# C1316G.net
KiCad netlist of a schematic drawn in EAGLE
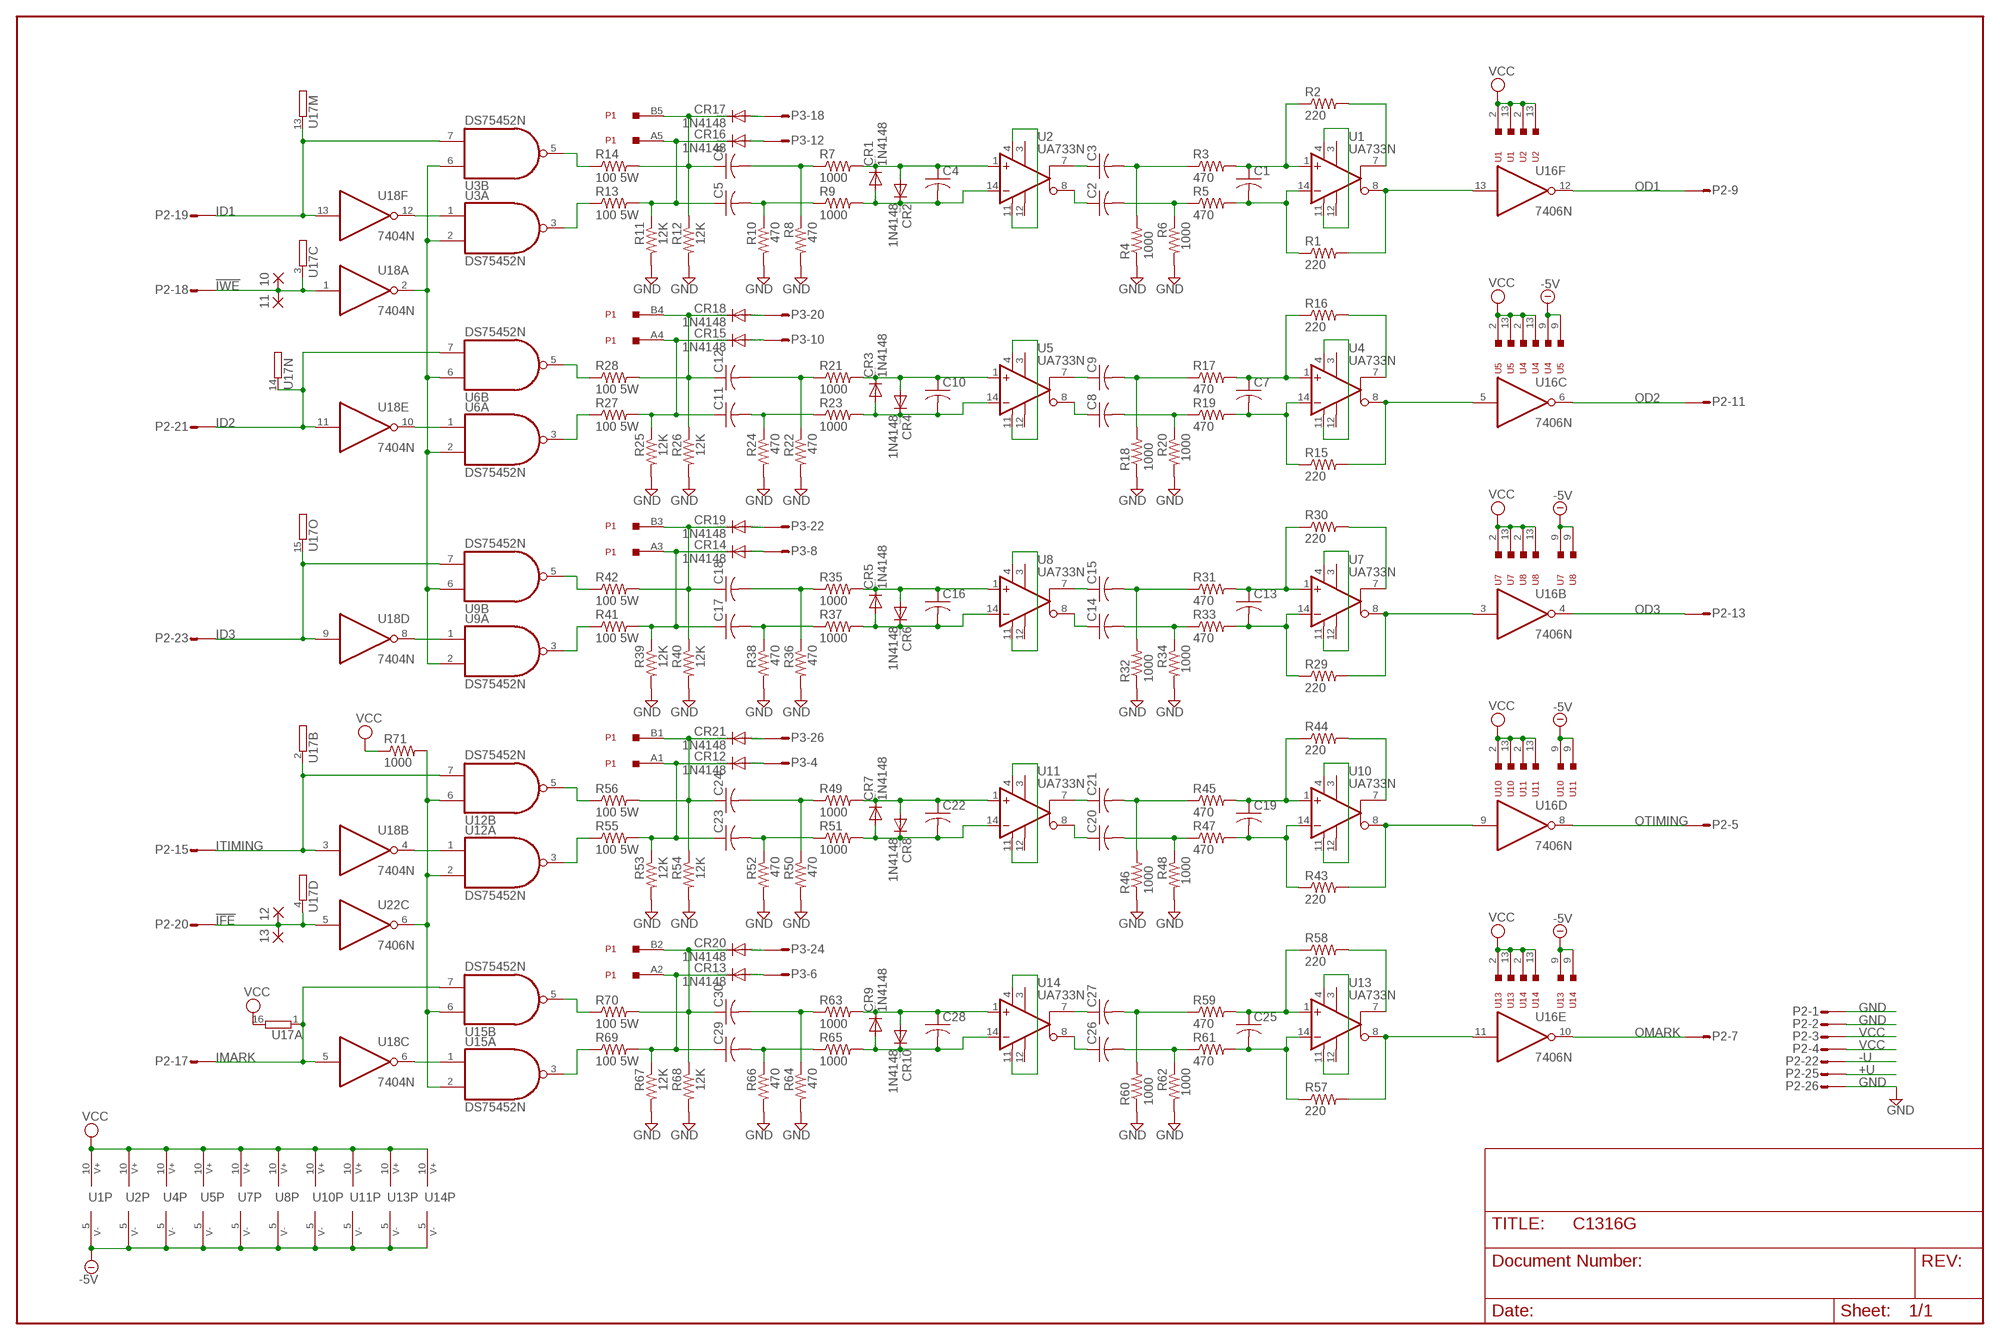
[diagram p0: schematic, sheet 1, part 1 of 2]
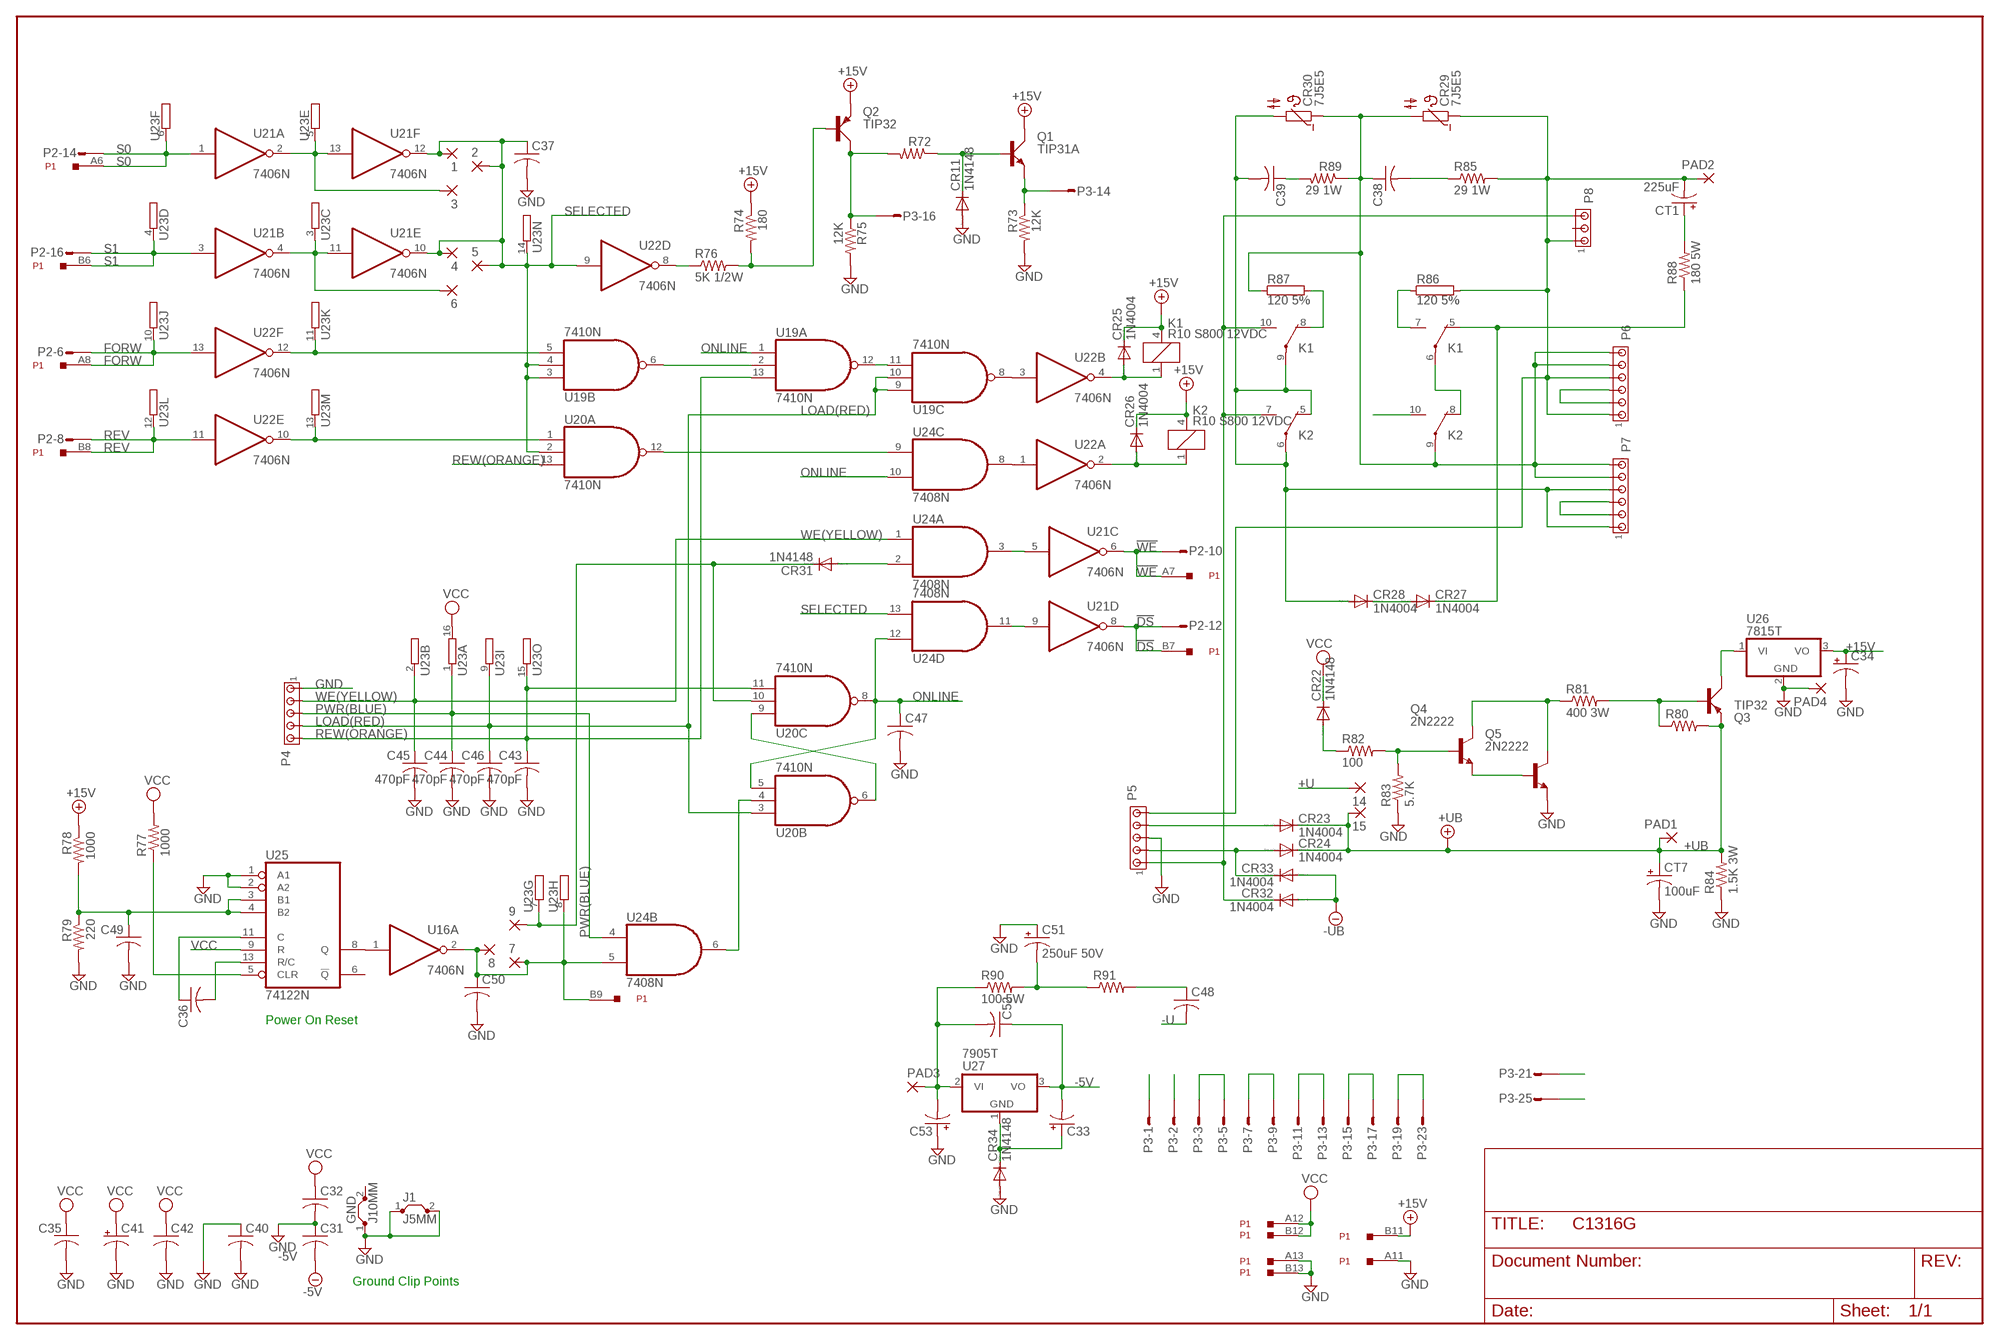
[diagram p1: schematic, sheet 1, part 2 of 2]

(export (version "E")
  (design (tool "Eeschema 10.0.6"))
  (components
    (comp (ref "1")
      (value "1,6/0,8")
      (footprint "eagle-import:1,6_0,8")
      (libsource (lib "eagle-import") (part "1,6/0,8"))
    )
    (comp (ref "2")
      (value "1,6/0,8")
      (footprint "eagle-import:1,6_0,8")
      (libsource (lib "eagle-import") (part "1,6/0,8"))
    )
    (comp (ref "3")
      (value "1,6/0,8")
      (footprint "eagle-import:1,6_0,8")
      (libsource (lib "eagle-import") (part "1,6/0,8"))
    )
    (comp (ref "4")
      (value "1,6/0,8")
      (footprint "eagle-import:1,6_0,8")
      (libsource (lib "eagle-import") (part "1,6/0,8"))
    )
    (comp (ref "5")
      (value "1,6/0,8")
      (footprint "eagle-import:1,6_0,8")
      (libsource (lib "eagle-import") (part "1,6/0,8"))
    )
    (comp (ref "6")
      (value "1,6/0,8")
      (footprint "eagle-import:1,6_0,8")
      (libsource (lib "eagle-import") (part "1,6/0,8"))
    )
    (comp (ref "7")
      (value "1,6/0,8")
      (footprint "eagle-import:1,6_0,8")
      (libsource (lib "eagle-import") (part "1,6/0,8"))
    )
    (comp (ref "8")
      (value "1,6/0,8")
      (footprint "eagle-import:1,6_0,8")
      (libsource (lib "eagle-import") (part "1,6/0,8"))
    )
    (comp (ref "9")
      (value "1,6/0,8")
      (footprint "eagle-import:1,6_0,8")
      (libsource (lib "eagle-import") (part "1,6/0,8"))
    )
    (comp (ref "10")
      (value "1,6/0,8")
      (footprint "eagle-import:1,6_0,8")
      (libsource (lib "eagle-import") (part "1,6/0,8"))
    )
    (comp (ref "11")
      (value "1,6/0,8")
      (footprint "eagle-import:1,6_0,8")
      (libsource (lib "eagle-import") (part "1,6/0,8"))
    )
    (comp (ref "12")
      (value "1,6/0,8")
      (footprint "eagle-import:1,6_0,8")
      (libsource (lib "eagle-import") (part "1,6/0,8"))
    )
    (comp (ref "13")
      (value "1,6/0,8")
      (footprint "eagle-import:1,6_0,8")
      (libsource (lib "eagle-import") (part "1,6/0,8"))
    )
    (comp (ref "14")
      (value "1,6/0,8")
      (footprint "eagle-import:1,6_0,8")
      (libsource (lib "eagle-import") (part "1,6/0,8"))
    )
    (comp (ref "15")
      (value "1,6/0,8")
      (footprint "eagle-import:1,6_0,8")
      (libsource (lib "eagle-import") (part "1,6/0,8"))
    )
    (comp (ref "C1")
      (value "C-US102-043X133")
      (footprint "eagle-import:C102-043X133")
      (libsource (lib "eagle-import") (part "C-US102-043X133"))
    )
    (comp (ref "C2")
      (value "C-US050-025X075")
      (footprint "eagle-import:C050-025X075")
      (libsource (lib "eagle-import") (part "C-US050-025X075"))
    )
    (comp (ref "C3")
      (value "C-US050-025X075")
      (footprint "eagle-import:C050-025X075")
      (libsource (lib "eagle-import") (part "C-US050-025X075"))
    )
    (comp (ref "C4")
      (value "C-US102-043X133")
      (footprint "eagle-import:C102-043X133")
      (libsource (lib "eagle-import") (part "C-US102-043X133"))
    )
    (comp (ref "C5")
      (value "C-US050-025X075")
      (footprint "eagle-import:C050-025X075")
      (libsource (lib "eagle-import") (part "C-US050-025X075"))
    )
    (comp (ref "C6")
      (value "C-US050-025X075")
      (footprint "eagle-import:C050-025X075")
      (libsource (lib "eagle-import") (part "C-US050-025X075"))
    )
    (comp (ref "C7")
      (value "C-US102-043X133")
      (footprint "eagle-import:C102-043X133")
      (libsource (lib "eagle-import") (part "C-US102-043X133"))
    )
    (comp (ref "C8")
      (value "C-US050-025X075")
      (footprint "eagle-import:C050-025X075")
      (libsource (lib "eagle-import") (part "C-US050-025X075"))
    )
    (comp (ref "C9")
      (value "C-US050-025X075")
      (footprint "eagle-import:C050-025X075")
      (libsource (lib "eagle-import") (part "C-US050-025X075"))
    )
    (comp (ref "C10")
      (value "C-US102-043X133")
      (footprint "eagle-import:C102-043X133")
      (libsource (lib "eagle-import") (part "C-US102-043X133"))
    )
    (comp (ref "C11")
      (value "C-US050-025X075")
      (footprint "eagle-import:C050-025X075")
      (libsource (lib "eagle-import") (part "C-US050-025X075"))
    )
    (comp (ref "C12")
      (value "C-US050-025X075")
      (footprint "eagle-import:C050-025X075")
      (libsource (lib "eagle-import") (part "C-US050-025X075"))
    )
    (comp (ref "C13")
      (value "C-US102-043X133")
      (footprint "eagle-import:C102-043X133")
      (libsource (lib "eagle-import") (part "C-US102-043X133"))
    )
    (comp (ref "C14")
      (value "C-US050-025X075")
      (footprint "eagle-import:C050-025X075")
      (libsource (lib "eagle-import") (part "C-US050-025X075"))
    )
    (comp (ref "C15")
      (value "C-US050-025X075")
      (footprint "eagle-import:C050-025X075")
      (libsource (lib "eagle-import") (part "C-US050-025X075"))
    )
    (comp (ref "C16")
      (value "C-US102-043X133")
      (footprint "eagle-import:C102-043X133")
      (libsource (lib "eagle-import") (part "C-US102-043X133"))
    )
    (comp (ref "C17")
      (value "C-US050-025X075")
      (footprint "eagle-import:C050-025X075")
      (libsource (lib "eagle-import") (part "C-US050-025X075"))
    )
    (comp (ref "C18")
      (value "C-US050-025X075")
      (footprint "eagle-import:C050-025X075")
      (libsource (lib "eagle-import") (part "C-US050-025X075"))
    )
    (comp (ref "C19")
      (value "C-US102-043X133")
      (footprint "eagle-import:C102-043X133")
      (libsource (lib "eagle-import") (part "C-US102-043X133"))
    )
    (comp (ref "C20")
      (value "C-US050-025X075")
      (footprint "eagle-import:C050-025X075")
      (libsource (lib "eagle-import") (part "C-US050-025X075"))
    )
    (comp (ref "C21")
      (value "C-US050-025X075")
      (footprint "eagle-import:C050-025X075")
      (libsource (lib "eagle-import") (part "C-US050-025X075"))
    )
    (comp (ref "C22")
      (value "C-US102-043X133")
      (footprint "eagle-import:C102-043X133")
      (libsource (lib "eagle-import") (part "C-US102-043X133"))
    )
    (comp (ref "C23")
      (value "C-US050-025X075")
      (footprint "eagle-import:C050-025X075")
      (libsource (lib "eagle-import") (part "C-US050-025X075"))
    )
    (comp (ref "C24")
      (value "C-US050-025X075")
      (footprint "eagle-import:C050-025X075")
      (libsource (lib "eagle-import") (part "C-US050-025X075"))
    )
    (comp (ref "C25")
      (value "C-US102-043X133")
      (footprint "eagle-import:C102-043X133")
      (libsource (lib "eagle-import") (part "C-US102-043X133"))
    )
    (comp (ref "C26")
      (value "C-US050-025X075")
      (footprint "eagle-import:C050-025X075")
      (libsource (lib "eagle-import") (part "C-US050-025X075"))
    )
    (comp (ref "C27")
      (value "C-US050-025X075")
      (footprint "eagle-import:C050-025X075")
      (libsource (lib "eagle-import") (part "C-US050-025X075"))
    )
    (comp (ref "C28")
      (value "C-US102-043X133")
      (footprint "eagle-import:C102-043X133")
      (libsource (lib "eagle-import") (part "C-US102-043X133"))
    )
    (comp (ref "C29")
      (value "C-US050-025X075")
      (footprint "eagle-import:C050-025X075")
      (libsource (lib "eagle-import") (part "C-US050-025X075"))
    )
    (comp (ref "C30")
      (value "C-US050-025X075")
      (footprint "eagle-import:C050-025X075")
      (libsource (lib "eagle-import") (part "C-US050-025X075"))
    )
    (comp (ref "C31")
      (value "C-US050-025X075")
      (footprint "eagle-import:C050-025X075")
      (libsource (lib "eagle-import") (part "C-US050-025X075"))
    )
    (comp (ref "C32")
      (value "C-US050-025X075")
      (footprint "eagle-import:C050-025X075")
      (libsource (lib "eagle-import") (part "C-US050-025X075"))
    )
    (comp (ref "C33")
      (value "CPOL-USB45181B")
      (footprint "eagle-import:B45181B")
      (libsource (lib "eagle-import") (part "CPOL-USB45181B"))
    )
    (comp (ref "C34")
      (value "CPOL-USB45181B")
      (footprint "eagle-import:B45181B")
      (libsource (lib "eagle-import") (part "CPOL-USB45181B"))
    )
    (comp (ref "C35")
      (value "C-US050-025X075")
      (footprint "eagle-import:C050-025X075")
      (libsource (lib "eagle-import") (part "C-US050-025X075"))
    )
    (comp (ref "C36")
      (value "C-US050-025X075")
      (footprint "eagle-import:C050-025X075")
      (libsource (lib "eagle-import") (part "C-US050-025X075"))
    )
    (comp (ref "C37")
      (value "C-US050-025X075")
      (footprint "eagle-import:C050-025X075")
      (libsource (lib "eagle-import") (part "C-US050-025X075"))
    )
    (comp (ref "C38")
      (value "C-US150-054X183")
      (footprint "eagle-import:C150-054X183")
      (libsource (lib "eagle-import") (part "C-US150-054X183"))
    )
    (comp (ref "C39")
      (value "C-US150-054X183")
      (footprint "eagle-import:C150-054X183")
      (libsource (lib "eagle-import") (part "C-US150-054X183"))
    )
    (comp (ref "C40")
      (value "C-US050-025X075")
      (footprint "eagle-import:C050-025X075")
      (libsource (lib "eagle-import") (part "C-US050-025X075"))
    )
    (comp (ref "C41")
      (value "CPOL-USE22-6AXIAL")
      (footprint "eagle-import:E22-6")
      (libsource (lib "eagle-import") (part "CPOL-USE22-6AXIAL"))
    )
    (comp (ref "C42")
      (value "C-US050-025X075")
      (footprint "eagle-import:C050-025X075")
      (libsource (lib "eagle-import") (part "C-US050-025X075"))
    )
    (comp (ref "C43")
      (value "470pF")
      (footprint "eagle-import:C050-025X075")
      (libsource (lib "eagle-import") (part "C-US050-025X075"))
    )
    (comp (ref "C44")
      (value "470pF")
      (footprint "eagle-import:C050-025X075")
      (libsource (lib "eagle-import") (part "C-US050-025X075"))
    )
    (comp (ref "C45")
      (value "470pF")
      (footprint "eagle-import:C050-025X075")
      (libsource (lib "eagle-import") (part "C-US050-025X075"))
    )
    (comp (ref "C46")
      (value "470pF")
      (footprint "eagle-import:C050-025X075")
      (libsource (lib "eagle-import") (part "C-US050-025X075"))
    )
    (comp (ref "C47")
      (value "C-US050-025X075")
      (footprint "eagle-import:C050-025X075")
      (libsource (lib "eagle-import") (part "C-US050-025X075"))
    )
    (comp (ref "C48")
      (value "C-US050-025X075")
      (footprint "eagle-import:C050-025X075")
      (libsource (lib "eagle-import") (part "C-US050-025X075"))
    )
    (comp (ref "C49")
      (value "C-US050-025X075")
      (footprint "eagle-import:C050-025X075")
      (libsource (lib "eagle-import") (part "C-US050-025X075"))
    )
    (comp (ref "C50")
      (value "C-US102-043X133")
      (footprint "eagle-import:C102-043X133")
      (libsource (lib "eagle-import") (part "C-US102-043X133"))
    )
    (comp (ref "C51")
      (value "250uF 50V")
      (footprint "eagle-import:E35-12")
      (libsource (lib "eagle-import") (part "CPOL-USE35-12AXIAL"))
    )
    (comp (ref "C52")
      (value "C-US050-025X075")
      (footprint "eagle-import:C050-025X075")
      (libsource (lib "eagle-import") (part "C-US050-025X075"))
    )
    (comp (ref "C53")
      (value "CPOL-USE22-6AXIAL")
      (footprint "eagle-import:E22-6")
      (libsource (lib "eagle-import") (part "CPOL-USE22-6AXIAL"))
    )
    (comp (ref "CR1")
      (value "1N4148")
      (footprint "eagle-import:DO35-10")
      (libsource (lib "eagle-import") (part "1N4148DO35-10"))
    )
    (comp (ref "CR2")
      (value "1N4148")
      (footprint "eagle-import:DO35-10")
      (libsource (lib "eagle-import") (part "1N4148DO35-10"))
    )
    (comp (ref "CR3")
      (value "1N4148")
      (footprint "eagle-import:DO35-10")
      (libsource (lib "eagle-import") (part "1N4148DO35-10"))
    )
    (comp (ref "CR4")
      (value "1N4148")
      (footprint "eagle-import:DO35-10")
      (libsource (lib "eagle-import") (part "1N4148DO35-10"))
    )
    (comp (ref "CR5")
      (value "1N4148")
      (footprint "eagle-import:DO35-10")
      (libsource (lib "eagle-import") (part "1N4148DO35-10"))
    )
    (comp (ref "CR6")
      (value "1N4148")
      (footprint "eagle-import:DO35-10")
      (libsource (lib "eagle-import") (part "1N4148DO35-10"))
    )
    (comp (ref "CR7")
      (value "1N4148")
      (footprint "eagle-import:DO35-10")
      (libsource (lib "eagle-import") (part "1N4148DO35-10"))
    )
    (comp (ref "CR8")
      (value "1N4148")
      (footprint "eagle-import:DO35-10")
      (libsource (lib "eagle-import") (part "1N4148DO35-10"))
    )
    (comp (ref "CR9")
      (value "1N4148")
      (footprint "eagle-import:DO35-10")
      (libsource (lib "eagle-import") (part "1N4148DO35-10"))
    )
    (comp (ref "CR10")
      (value "1N4148")
      (footprint "eagle-import:DO35-10")
      (libsource (lib "eagle-import") (part "1N4148DO35-10"))
    )
    (comp (ref "CR11")
      (value "1N4148")
      (footprint "eagle-import:DO35-10")
      (libsource (lib "eagle-import") (part "1N4148DO35-10"))
    )
    (comp (ref "CR12")
      (value "1N4148")
      (footprint "eagle-import:DO35-10")
      (libsource (lib "eagle-import") (part "1N4148DO35-10"))
    )
    (comp (ref "CR13")
      (value "1N4148")
      (footprint "eagle-import:DO35-10")
      (libsource (lib "eagle-import") (part "1N4148DO35-10"))
    )
    (comp (ref "CR14")
      (value "1N4148")
      (footprint "eagle-import:DO35-10")
      (libsource (lib "eagle-import") (part "1N4148DO35-10"))
    )
    (comp (ref "CR15")
      (value "1N4148")
      (footprint "eagle-import:DO35-10")
      (libsource (lib "eagle-import") (part "1N4148DO35-10"))
    )
    (comp (ref "CR16")
      (value "1N4148")
      (footprint "eagle-import:DO35-10")
      (libsource (lib "eagle-import") (part "1N4148DO35-10"))
    )
    (comp (ref "CR17")
      (value "1N4148")
      (footprint "eagle-import:DO35-10")
      (libsource (lib "eagle-import") (part "1N4148DO35-10"))
    )
    (comp (ref "CR18")
      (value "1N4148")
      (footprint "eagle-import:DO35-10")
      (libsource (lib "eagle-import") (part "1N4148DO35-10"))
    )
    (comp (ref "CR19")
      (value "1N4148")
      (footprint "eagle-import:DO35-10")
      (libsource (lib "eagle-import") (part "1N4148DO35-10"))
    )
    (comp (ref "CR20")
      (value "1N4148")
      (footprint "eagle-import:DO35-10")
      (libsource (lib "eagle-import") (part "1N4148DO35-10"))
    )
    (comp (ref "CR21")
      (value "1N4148")
      (footprint "eagle-import:DO35-10")
      (libsource (lib "eagle-import") (part "1N4148DO35-10"))
    )
    (comp (ref "CR22")
      (value "1N4148")
      (footprint "eagle-import:DO35-10")
      (libsource (lib "eagle-import") (part "1N4148DO35-10"))
    )
    (comp (ref "CR23")
      (value "1N4004")
      (footprint "eagle-import:DO41-10")
      (libsource (lib "eagle-import") (part "1N4004"))
    )
    (comp (ref "CR24")
      (value "1N4004")
      (footprint "eagle-import:DO41-10")
      (libsource (lib "eagle-import") (part "1N4004"))
    )
    (comp (ref "CR25")
      (value "1N4004")
      (footprint "eagle-import:DO41-10")
      (libsource (lib "eagle-import") (part "1N4004"))
    )
    (comp (ref "CR26")
      (value "1N4004")
      (footprint "eagle-import:DO41-10")
      (libsource (lib "eagle-import") (part "1N4004"))
    )
    (comp (ref "CR27")
      (value "1N4004")
      (footprint "eagle-import:DO41-10")
      (libsource (lib "eagle-import") (part "1N4004"))
    )
    (comp (ref "CR28")
      (value "1N4004")
      (footprint "eagle-import:DO41-10")
      (libsource (lib "eagle-import") (part "1N4004"))
    )
    (comp (ref "CR29")
      (value "7J5E5")
      (footprint "eagle-import:N644B")
      (libsource (lib "eagle-import") (part "NTC644B"))
    )
    (comp (ref "CR30")
      (value "7J5E5")
      (footprint "eagle-import:N644B")
      (libsource (lib "eagle-import") (part "NTC644B"))
    )
    (comp (ref "CR31")
      (value "1N4148")
      (footprint "eagle-import:DO35-10")
      (libsource (lib "eagle-import") (part "1N4148DO35-10"))
    )
    (comp (ref "CR32")
      (value "1N4004")
      (footprint "eagle-import:DO41-10")
      (libsource (lib "eagle-import") (part "1N4004"))
    )
    (comp (ref "CR33")
      (value "1N4004")
      (footprint "eagle-import:DO41-10")
      (libsource (lib "eagle-import") (part "1N4004"))
    )
    (comp (ref "CR34")
      (value "1N4148")
      (footprint "eagle-import:DO35-10")
      (libsource (lib "eagle-import") (part "1N4148DO35-10"))
    )
    (comp (ref "CT1")
      (value "225uF")
      (footprint "eagle-import:E55-25")
      (libsource (lib "eagle-import") (part "CPOL-USE55-25AXIAL"))
    )
    (comp (ref "CT7")
      (value "100uF")
      (footprint "eagle-import:E55-25")
      (libsource (lib "eagle-import") (part "CPOL-USE55-25AXIAL"))
    )
    (comp (ref "GND")
      (value "J10MM")
      (footprint "eagle-import:10")
      (libsource (lib "eagle-import") (part "J10MM"))
    )
    (comp (ref "J1")
      (value "J5MM")
      (footprint "eagle-import:05")
      (libsource (lib "eagle-import") (part "J5MM"))
    )
    (comp (ref "K1")
      (value "R10 S800 12VDC")
      (footprint "eagle-import:R10")
      (libsource (lib "eagle-import") (part "DPDTR10"))
    )
    (comp (ref "K2")
      (value "R10 S800 12VDC")
      (footprint "eagle-import:R10")
      (libsource (lib "eagle-import") (part "DPDTR10"))
    )
    (comp (ref "P1")
      (value "EDGE13X2")
      (footprint "eagle-import:EDGE13X2")
      (libsource (lib "eagle-import") (part "EDGE13X2"))
    )
    (comp (ref "P2")
      (value "26HS")
      (footprint "eagle-import:26H")
      (libsource (lib "eagle-import") (part "26HS"))
    )
    (comp (ref "P3")
      (value "26VS")
      (footprint "eagle-import:26V")
      (libsource (lib "eagle-import") (part "26VS"))
    )
    (comp (ref "P4")
      (value "MTA05-156")
      (footprint "eagle-import:1X5MTA")
      (libsource (lib "eagle-import") (part "MTA05-156"))
    )
    (comp (ref "P5")
      (value "MTA05-156")
      (footprint "eagle-import:1X5MTA")
      (libsource (lib "eagle-import") (part "MTA05-156"))
    )
    (comp (ref "P6")
      (value "MTA06-156")
      (footprint "eagle-import:1X6MTA")
      (libsource (lib "eagle-import") (part "MTA06-156"))
    )
    (comp (ref "P7")
      (value "MTA06-156")
      (footprint "eagle-import:1X6MTA")
      (libsource (lib "eagle-import") (part "MTA06-156"))
    )
    (comp (ref "P8")
      (value "MTA03-156")
      (footprint "eagle-import:1X3MTA")
      (libsource (lib "eagle-import") (part "MTA03-156"))
    )
    (comp (ref "PAD1")
      (value "3,81/1,1")
      (footprint "eagle-import:3,81_1,1")
      (libsource (lib "eagle-import") (part "3,81/1,1"))
    )
    (comp (ref "PAD2")
      (value "3,81/1,1")
      (footprint "eagle-import:3,81_1,1")
      (libsource (lib "eagle-import") (part "3,81/1,1"))
    )
    (comp (ref "PAD3")
      (value "1,6/0,8")
      (footprint "eagle-import:1,6_0,8")
      (libsource (lib "eagle-import") (part "1,6/0,8"))
    )
    (comp (ref "PAD4")
      (value "1,6/0,8")
      (footprint "eagle-import:1,6_0,8")
      (libsource (lib "eagle-import") (part "1,6/0,8"))
    )
    (comp (ref "Q1")
      (value "TIP31A")
      (footprint "eagle-import:TO220AV")
      (libsource (lib "eagle-import") (part "TIP41C"))
    )
    (comp (ref "Q2")
      (value "TIP32")
      (footprint "eagle-import:TO220AV")
      (libsource (lib "eagle-import") (part "TIP42C"))
    )
    (comp (ref "Q3")
      (value "TIP32")
      (footprint "eagle-import:TO220AV")
      (libsource (lib "eagle-import") (part "TIP42C"))
    )
    (comp (ref "Q4")
      (value "2N2222")
      (footprint "eagle-import:TO5")
      (libsource (lib "eagle-import") (part "2N2219"))
    )
    (comp (ref "Q5")
      (value "2N2222")
      (footprint "eagle-import:TO5")
      (libsource (lib "eagle-import") (part "2N2219"))
    )
    (comp (ref "R1")
      (value "220")
      (footprint "eagle-import:0207_10")
      (libsource (lib "eagle-import") (part "R-US_0207/10"))
    )
    (comp (ref "R2")
      (value "220")
      (footprint "eagle-import:0207_10")
      (libsource (lib "eagle-import") (part "R-US_0207/10"))
    )
    (comp (ref "R3")
      (value "470")
      (footprint "eagle-import:0207_10")
      (libsource (lib "eagle-import") (part "R-US_0207/10"))
    )
    (comp (ref "R4")
      (value "1000")
      (footprint "eagle-import:0207_10")
      (libsource (lib "eagle-import") (part "R-US_0207/10"))
    )
    (comp (ref "R5")
      (value "470")
      (footprint "eagle-import:0207_10")
      (libsource (lib "eagle-import") (part "R-US_0207/10"))
    )
    (comp (ref "R6")
      (value "1000")
      (footprint "eagle-import:0207_10")
      (libsource (lib "eagle-import") (part "R-US_0207/10"))
    )
    (comp (ref "R7")
      (value "1000")
      (footprint "eagle-import:0207_10")
      (libsource (lib "eagle-import") (part "R-US_0207/10"))
    )
    (comp (ref "R8")
      (value "470")
      (footprint "eagle-import:0207_10")
      (libsource (lib "eagle-import") (part "R-US_0207/10"))
    )
    (comp (ref "R9")
      (value "1000")
      (footprint "eagle-import:0207_10")
      (libsource (lib "eagle-import") (part "R-US_0207/10"))
    )
    (comp (ref "R10")
      (value "470")
      (footprint "eagle-import:0207_10")
      (libsource (lib "eagle-import") (part "R-US_0207/10"))
    )
    (comp (ref "R11")
      (value "12K")
      (footprint "eagle-import:0207_10")
      (libsource (lib "eagle-import") (part "R-US_0207/10"))
    )
    (comp (ref "R12")
      (value "12K")
      (footprint "eagle-import:0207_10")
      (libsource (lib "eagle-import") (part "R-US_0207/10"))
    )
    (comp (ref "R13")
      (value "100 5W")
      (footprint "eagle-import:0414_20")
      (libsource (lib "eagle-import") (part "R-US_0414/20"))
    )
    (comp (ref "R14")
      (value "100 5W")
      (footprint "eagle-import:0414_20")
      (libsource (lib "eagle-import") (part "R-US_0414/20"))
    )
    (comp (ref "R15")
      (value "220")
      (footprint "eagle-import:0207_10")
      (libsource (lib "eagle-import") (part "R-US_0207/10"))
    )
    (comp (ref "R16")
      (value "220")
      (footprint "eagle-import:0207_10")
      (libsource (lib "eagle-import") (part "R-US_0207/10"))
    )
    (comp (ref "R17")
      (value "470")
      (footprint "eagle-import:0207_10")
      (libsource (lib "eagle-import") (part "R-US_0207/10"))
    )
    (comp (ref "R18")
      (value "1000")
      (footprint "eagle-import:0207_10")
      (libsource (lib "eagle-import") (part "R-US_0207/10"))
    )
    (comp (ref "R19")
      (value "470")
      (footprint "eagle-import:0207_10")
      (libsource (lib "eagle-import") (part "R-US_0207/10"))
    )
    (comp (ref "R20")
      (value "1000")
      (footprint "eagle-import:0207_10")
      (libsource (lib "eagle-import") (part "R-US_0207/10"))
    )
    (comp (ref "R21")
      (value "1000")
      (footprint "eagle-import:0207_10")
      (libsource (lib "eagle-import") (part "R-US_0207/10"))
    )
    (comp (ref "R22")
      (value "470")
      (footprint "eagle-import:0207_10")
      (libsource (lib "eagle-import") (part "R-US_0207/10"))
    )
    (comp (ref "R23")
      (value "1000")
      (footprint "eagle-import:0207_10")
      (libsource (lib "eagle-import") (part "R-US_0207/10"))
    )
    (comp (ref "R24")
      (value "470")
      (footprint "eagle-import:0207_10")
      (libsource (lib "eagle-import") (part "R-US_0207/10"))
    )
    (comp (ref "R25")
      (value "12K")
      (footprint "eagle-import:0207_10")
      (libsource (lib "eagle-import") (part "R-US_0207/10"))
    )
    (comp (ref "R26")
      (value "12K")
      (footprint "eagle-import:0207_10")
      (libsource (lib "eagle-import") (part "R-US_0207/10"))
    )
    (comp (ref "R27")
      (value "100 5W")
      (footprint "eagle-import:0414_20")
      (libsource (lib "eagle-import") (part "R-US_0414/20"))
    )
    (comp (ref "R28")
      (value "100 5W")
      (footprint "eagle-import:0414_20")
      (libsource (lib "eagle-import") (part "R-US_0414/20"))
    )
    (comp (ref "R29")
      (value "220")
      (footprint "eagle-import:0207_10")
      (libsource (lib "eagle-import") (part "R-US_0207/10"))
    )
    (comp (ref "R30")
      (value "220")
      (footprint "eagle-import:0207_10")
      (libsource (lib "eagle-import") (part "R-US_0207/10"))
    )
    (comp (ref "R31")
      (value "470")
      (footprint "eagle-import:0207_10")
      (libsource (lib "eagle-import") (part "R-US_0207/10"))
    )
    (comp (ref "R32")
      (value "1000")
      (footprint "eagle-import:0207_10")
      (libsource (lib "eagle-import") (part "R-US_0207/10"))
    )
    (comp (ref "R33")
      (value "470")
      (footprint "eagle-import:0207_10")
      (libsource (lib "eagle-import") (part "R-US_0207/10"))
    )
    (comp (ref "R34")
      (value "1000")
      (footprint "eagle-import:0207_10")
      (libsource (lib "eagle-import") (part "R-US_0207/10"))
    )
    (comp (ref "R35")
      (value "1000")
      (footprint "eagle-import:0207_10")
      (libsource (lib "eagle-import") (part "R-US_0207/10"))
    )
    (comp (ref "R36")
      (value "470")
      (footprint "eagle-import:0207_10")
      (libsource (lib "eagle-import") (part "R-US_0207/10"))
    )
    (comp (ref "R37")
      (value "1000")
      (footprint "eagle-import:0207_10")
      (libsource (lib "eagle-import") (part "R-US_0207/10"))
    )
    (comp (ref "R38")
      (value "470")
      (footprint "eagle-import:0207_10")
      (libsource (lib "eagle-import") (part "R-US_0207/10"))
    )
    (comp (ref "R39")
      (value "12K")
      (footprint "eagle-import:0207_10")
      (libsource (lib "eagle-import") (part "R-US_0207/10"))
    )
    (comp (ref "R40")
      (value "12K")
      (footprint "eagle-import:0207_10")
      (libsource (lib "eagle-import") (part "R-US_0207/10"))
    )
    (comp (ref "R41")
      (value "100 5W")
      (footprint "eagle-import:0414_20")
      (libsource (lib "eagle-import") (part "R-US_0414/20"))
    )
    (comp (ref "R42")
      (value "100 5W")
      (footprint "eagle-import:0414_20")
      (libsource (lib "eagle-import") (part "R-US_0414/20"))
    )
    (comp (ref "R43")
      (value "220")
      (footprint "eagle-import:0207_10")
      (libsource (lib "eagle-import") (part "R-US_0207/10"))
    )
    (comp (ref "R44")
      (value "220")
      (footprint "eagle-import:0207_10")
      (libsource (lib "eagle-import") (part "R-US_0207/10"))
    )
    (comp (ref "R45")
      (value "470")
      (footprint "eagle-import:0207_10")
      (libsource (lib "eagle-import") (part "R-US_0207/10"))
    )
    (comp (ref "R46")
      (value "1000")
      (footprint "eagle-import:0207_10")
      (libsource (lib "eagle-import") (part "R-US_0207/10"))
    )
    (comp (ref "R47")
      (value "470")
      (footprint "eagle-import:0207_10")
      (libsource (lib "eagle-import") (part "R-US_0207/10"))
    )
    (comp (ref "R48")
      (value "1000")
      (footprint "eagle-import:0207_10")
      (libsource (lib "eagle-import") (part "R-US_0207/10"))
    )
    (comp (ref "R49")
      (value "1000")
      (footprint "eagle-import:0207_10")
      (libsource (lib "eagle-import") (part "R-US_0207/10"))
    )
    (comp (ref "R50")
      (value "470")
      (footprint "eagle-import:0207_10")
      (libsource (lib "eagle-import") (part "R-US_0207/10"))
    )
    (comp (ref "R51")
      (value "1000")
      (footprint "eagle-import:0207_10")
      (libsource (lib "eagle-import") (part "R-US_0207/10"))
    )
    (comp (ref "R52")
      (value "470")
      (footprint "eagle-import:0207_10")
      (libsource (lib "eagle-import") (part "R-US_0207/10"))
    )
    (comp (ref "R53")
      (value "12K")
      (footprint "eagle-import:0207_10")
      (libsource (lib "eagle-import") (part "R-US_0207/10"))
    )
    (comp (ref "R54")
      (value "12K")
      (footprint "eagle-import:0207_10")
      (libsource (lib "eagle-import") (part "R-US_0207/10"))
    )
    (comp (ref "R55")
      (value "100 5W")
      (footprint "eagle-import:0414_20")
      (libsource (lib "eagle-import") (part "R-US_0414/20"))
    )
    (comp (ref "R56")
      (value "100 5W")
      (footprint "eagle-import:0414_20")
      (libsource (lib "eagle-import") (part "R-US_0414/20"))
    )
    (comp (ref "R57")
      (value "220")
      (footprint "eagle-import:0207_10")
      (libsource (lib "eagle-import") (part "R-US_0207/10"))
    )
    (comp (ref "R58")
      (value "220")
      (footprint "eagle-import:0207_10")
      (libsource (lib "eagle-import") (part "R-US_0207/10"))
    )
    (comp (ref "R59")
      (value "470")
      (footprint "eagle-import:0207_10")
      (libsource (lib "eagle-import") (part "R-US_0207/10"))
    )
    (comp (ref "R60")
      (value "1000")
      (footprint "eagle-import:0207_10")
      (libsource (lib "eagle-import") (part "R-US_0207/10"))
    )
    (comp (ref "R61")
      (value "470")
      (footprint "eagle-import:0207_10")
      (libsource (lib "eagle-import") (part "R-US_0207/10"))
    )
    (comp (ref "R62")
      (value "1000")
      (footprint "eagle-import:0207_10")
      (libsource (lib "eagle-import") (part "R-US_0207/10"))
    )
    (comp (ref "R63")
      (value "1000")
      (footprint "eagle-import:0207_10")
      (libsource (lib "eagle-import") (part "R-US_0207/10"))
    )
    (comp (ref "R64")
      (value "470")
      (footprint "eagle-import:0207_10")
      (libsource (lib "eagle-import") (part "R-US_0207/10"))
    )
    (comp (ref "R65")
      (value "1000")
      (footprint "eagle-import:0207_10")
      (libsource (lib "eagle-import") (part "R-US_0207/10"))
    )
    (comp (ref "R66")
      (value "470")
      (footprint "eagle-import:0207_10")
      (libsource (lib "eagle-import") (part "R-US_0207/10"))
    )
    (comp (ref "R67")
      (value "12K")
      (footprint "eagle-import:0207_10")
      (libsource (lib "eagle-import") (part "R-US_0207/10"))
    )
    (comp (ref "R68")
      (value "12K")
      (footprint "eagle-import:0207_10")
      (libsource (lib "eagle-import") (part "R-US_0207/10"))
    )
    (comp (ref "R69")
      (value "100 5W")
      (footprint "eagle-import:0414_20")
      (libsource (lib "eagle-import") (part "R-US_0414/20"))
    )
    (comp (ref "R70")
      (value "100 5W")
      (footprint "eagle-import:0414_20")
      (libsource (lib "eagle-import") (part "R-US_0414/20"))
    )
    (comp (ref "R71")
      (value "1000")
      (footprint "eagle-import:0207_10")
      (libsource (lib "eagle-import") (part "R-US_0207/10"))
    )
    (comp (ref "R72")
      (value "R-US_0207/10")
      (footprint "eagle-import:0207_10")
      (libsource (lib "eagle-import") (part "R-US_0207/10"))
    )
    (comp (ref "R73")
      (value "12K")
      (footprint "eagle-import:0207_10")
      (libsource (lib "eagle-import") (part "R-US_0207/10"))
    )
    (comp (ref "R74")
      (value "180")
      (footprint "eagle-import:0207_10")
      (libsource (lib "eagle-import") (part "R-US_0207/10"))
    )
    (comp (ref "R75")
      (value "12K")
      (footprint "eagle-import:0207_10")
      (libsource (lib "eagle-import") (part "R-US_0207/10"))
    )
    (comp (ref "R76")
      (value "5K 1/2W")
      (footprint "eagle-import:0411_15")
      (libsource (lib "eagle-import") (part "R-US_0411/15"))
    )
    (comp (ref "R77")
      (value "1000")
      (footprint "eagle-import:0207_10")
      (libsource (lib "eagle-import") (part "R-US_0207/10"))
    )
    (comp (ref "R78")
      (value "1000")
      (footprint "eagle-import:0207_10")
      (libsource (lib "eagle-import") (part "R-US_0207/10"))
    )
    (comp (ref "R79")
      (value "220")
      (footprint "eagle-import:0207_10")
      (libsource (lib "eagle-import") (part "R-US_0207/10"))
    )
    (comp (ref "R80")
      (value "R-US_0207/10")
      (footprint "eagle-import:0207_10")
      (libsource (lib "eagle-import") (part "R-US_0207/10"))
    )
    (comp (ref "R81")
      (value "400 3W")
      (footprint "eagle-import:0617_22")
      (libsource (lib "eagle-import") (part "R-US_0617/22"))
    )
    (comp (ref "R82")
      (value "100")
      (footprint "eagle-import:0207_10")
      (libsource (lib "eagle-import") (part "R-US_0207/10"))
    )
    (comp (ref "R83")
      (value "5.7K")
      (footprint "eagle-import:0207_10")
      (libsource (lib "eagle-import") (part "R-US_0207/10"))
    )
    (comp (ref "R84")
      (value "1.5K 3W")
      (footprint "eagle-import:0414_20")
      (libsource (lib "eagle-import") (part "R-US_0414/20"))
    )
    (comp (ref "R85")
      (value "29 1W")
      (footprint "eagle-import:0411_15")
      (libsource (lib "eagle-import") (part "R-US_0411/15"))
    )
    (comp (ref "R86")
      (value "120 5%")
      (footprint "eagle-import:KH216-8")
      (libsource (lib "eagle-import") (part "RKH216-8"))
    )
    (comp (ref "R87")
      (value "120 5%")
      (footprint "eagle-import:KH216-8")
      (libsource (lib "eagle-import") (part "RKH216-8"))
    )
    (comp (ref "R88")
      (value "180 5W")
      (footprint "eagle-import:0414_20")
      (libsource (lib "eagle-import") (part "R-US_0414/20"))
    )
    (comp (ref "R89")
      (value "29 1W")
      (footprint "eagle-import:0411_15")
      (libsource (lib "eagle-import") (part "R-US_0411/15"))
    )
    (comp (ref "R90")
      (value "100 5W")
      (footprint "eagle-import:0414_20")
      (libsource (lib "eagle-import") (part "R-US_0414/20"))
    )
    (comp (ref "R91")
      (value "R-US_0207/10")
      (footprint "eagle-import:0207_10")
      (libsource (lib "eagle-import") (part "R-US_0207/10"))
    )
    (comp (ref "U1")
      (value "UA733N")
      (footprint "eagle-import:DIL14")
      (libsource (lib "eagle-import") (part "UA733N"))
    )
    (comp (ref "U2")
      (value "UA733N")
      (footprint "eagle-import:DIL14")
      (libsource (lib "eagle-import") (part "UA733N"))
    )
    (comp (ref "U3")
      (value "DS75452N")
      (footprint "eagle-import:DIL08")
      (libsource (lib "eagle-import") (part "DS75452N"))
    )
    (comp (ref "U4")
      (value "UA733N")
      (footprint "eagle-import:DIL14")
      (libsource (lib "eagle-import") (part "UA733N"))
    )
    (comp (ref "U5")
      (value "UA733N")
      (footprint "eagle-import:DIL14")
      (libsource (lib "eagle-import") (part "UA733N"))
    )
    (comp (ref "U6")
      (value "DS75452N")
      (footprint "eagle-import:DIL08")
      (libsource (lib "eagle-import") (part "DS75452N"))
    )
    (comp (ref "U7")
      (value "UA733N")
      (footprint "eagle-import:DIL14")
      (libsource (lib "eagle-import") (part "UA733N"))
    )
    (comp (ref "U8")
      (value "UA733N")
      (footprint "eagle-import:DIL14")
      (libsource (lib "eagle-import") (part "UA733N"))
    )
    (comp (ref "U9")
      (value "DS75452N")
      (footprint "eagle-import:DIL08")
      (libsource (lib "eagle-import") (part "DS75452N"))
    )
    (comp (ref "U10")
      (value "UA733N")
      (footprint "eagle-import:DIL14")
      (libsource (lib "eagle-import") (part "UA733N"))
    )
    (comp (ref "U11")
      (value "UA733N")
      (footprint "eagle-import:DIL14")
      (libsource (lib "eagle-import") (part "UA733N"))
    )
    (comp (ref "U12")
      (value "DS75452N")
      (footprint "eagle-import:DIL08")
      (libsource (lib "eagle-import") (part "DS75452N"))
    )
    (comp (ref "U13")
      (value "UA733N")
      (footprint "eagle-import:DIL14")
      (libsource (lib "eagle-import") (part "UA733N"))
    )
    (comp (ref "U14")
      (value "UA733N")
      (footprint "eagle-import:DIL14")
      (libsource (lib "eagle-import") (part "UA733N"))
    )
    (comp (ref "U15")
      (value "DS75452N")
      (footprint "eagle-import:DIL08")
      (libsource (lib "eagle-import") (part "DS75452N"))
    )
    (comp (ref "U16")
      (value "7406N")
      (footprint "eagle-import:DIL14")
      (libsource (lib "eagle-import") (part "7406N"))
    )
    (comp (ref "U17")
      (value "E15R")
      (footprint "eagle-import:DIL16")
      (libsource (lib "eagle-import") (part "E15R"))
    )
    (comp (ref "U18")
      (value "7404N")
      (footprint "eagle-import:DIL14")
      (libsource (lib "eagle-import") (part "7404N"))
    )
    (comp (ref "U19")
      (value "7410N")
      (footprint "eagle-import:DIL14")
      (libsource (lib "eagle-import") (part "7410N"))
    )
    (comp (ref "U20")
      (value "7410N")
      (footprint "eagle-import:DIL14")
      (libsource (lib "eagle-import") (part "7410N"))
    )
    (comp (ref "U21")
      (value "7406N")
      (footprint "eagle-import:DIL14")
      (libsource (lib "eagle-import") (part "7406N"))
    )
    (comp (ref "U22")
      (value "7406N")
      (footprint "eagle-import:DIL14")
      (libsource (lib "eagle-import") (part "7406N"))
    )
    (comp (ref "U23")
      (value "E15R")
      (footprint "eagle-import:DIL16")
      (libsource (lib "eagle-import") (part "E15R"))
    )
    (comp (ref "U24")
      (value "7408N")
      (footprint "eagle-import:DIL14")
      (libsource (lib "eagle-import") (part "7408NLS"))
    )
    (comp (ref "U25")
      (value "74122N")
      (footprint "eagle-import:DIL14")
      (libsource (lib "eagle-import") (part "74122NLS"))
    )
    (comp (ref "U26")
      (value "7815T")
      (footprint "eagle-import:TO220H")
      (libsource (lib "eagle-import") (part "78T05"))
    )
    (comp (ref "U27")
      (value "7905T")
      (footprint "eagle-import:TO220H")
      (libsource (lib "eagle-import") (part "79T05"))
    )
  )
  (nets
    (net (code "1") (name "+15V") (class "Default")
      (node (ref "C34") (pin "+") (pinfunction "+_+") (pintype "passive"))
      (node (ref "CR25") (pin "C") (pinfunction "C_C") (pintype "passive"))
      (node (ref "CR26") (pin "C") (pinfunction "C_C") (pintype "passive"))
      (node (ref "K1") (pin "4") (pinfunction "7_4") (pintype "passive"))
      (node (ref "K2") (pin "4") (pinfunction "7_4") (pintype "passive"))
      (node (ref "P1") (pin "B11") (pinfunction "P$2_B11") (pintype "passive"))
      (node (ref "Q1") (pin "C") (pinfunction "C_C") (pintype "passive"))
      (node (ref "Q2") (pin "E") (pinfunction "E_E") (pintype "passive"))
      (node (ref "R74") (pin "1") (pinfunction "1_1") (pintype "passive"))
      (node (ref "R78") (pin "1") (pinfunction "1_1") (pintype "passive"))
      (node (ref "U26") (pin "3") (pinfunction "VO_3") (pintype "passive"))
    )
    (net (code "2") (name "+UB") (class "Default")
      (node (ref "15") (pin "1") (pinfunction "P_1") (pintype "passive"))
      (node (ref "CR23") (pin "C") (pinfunction "C_C") (pintype "passive"))
      (node (ref "CR24") (pin "C") (pinfunction "C_C") (pintype "passive"))
      (node (ref "CT7") (pin "+") (pinfunction "+_+") (pintype "passive"))
      (node (ref "PAD1") (pin "1") (pinfunction "P_1") (pintype "passive"))
      (node (ref "Q3") (pin "E") (pinfunction "E_E") (pintype "passive"))
      (node (ref "R80") (pin "2") (pinfunction "2_2") (pintype "passive"))
      (node (ref "R84") (pin "2") (pinfunction "2_2") (pintype "passive"))
    )
    (net (code "3") (name "-5V") (class "Default")
      (node (ref "C31") (pin "2") (pinfunction "2_2") (pintype "passive"))
      (node (ref "C33") (pin "-") (pinfunction "-_-") (pintype "passive"))
      (node (ref "C52") (pin "1") (pinfunction "1_1") (pintype "passive"))
      (node (ref "U1") (pin "5") (pinfunction "V-_5") (pintype "power_in"))
      (node (ref "U10") (pin "5") (pinfunction "V-_5") (pintype "power_in"))
      (node (ref "U10") (pin "9") (pinfunction "P$2_9") (pintype "passive"))
      (node (ref "U11") (pin "5") (pinfunction "V-_5") (pintype "power_in"))
      (node (ref "U11") (pin "9") (pinfunction "P$2_9") (pintype "passive"))
      (node (ref "U13") (pin "5") (pinfunction "V-_5") (pintype "power_in"))
      (node (ref "U13") (pin "9") (pinfunction "P$2_9") (pintype "passive"))
      (node (ref "U14") (pin "5") (pinfunction "V-_5") (pintype "power_in"))
      (node (ref "U14") (pin "9") (pinfunction "P$2_9") (pintype "passive"))
      (node (ref "U2") (pin "5") (pinfunction "V-_5") (pintype "power_in"))
      (node (ref "U27") (pin "3") (pinfunction "VO_3") (pintype "passive"))
      (node (ref "U4") (pin "5") (pinfunction "V-_5") (pintype "power_in"))
      (node (ref "U4") (pin "9") (pinfunction "P$2_9") (pintype "passive"))
      (node (ref "U5") (pin "5") (pinfunction "V-_5") (pintype "power_in"))
      (node (ref "U5") (pin "9") (pinfunction "P$2_9") (pintype "passive"))
      (node (ref "U7") (pin "5") (pinfunction "V-_5") (pintype "power_in"))
      (node (ref "U7") (pin "9") (pinfunction "P$2_9") (pintype "passive"))
      (node (ref "U8") (pin "5") (pinfunction "V-_5") (pintype "power_in"))
      (node (ref "U8") (pin "9") (pinfunction "P$2_9") (pintype "passive"))
    )
    (net (code "4") (name "-UB") (class "Default")
      (node (ref "CR32") (pin "A") (pinfunction "A_A") (pintype "passive"))
      (node (ref "CR33") (pin "A") (pinfunction "A_A") (pintype "passive"))
    )
    (net (code "5") (name "/+U") (class "Default")
      (node (ref "14") (pin "1") (pinfunction "P_1") (pintype "passive"))
      (node (ref "P2") (pin "25") (pinfunction "S_25") (pintype "passive"))
    )
    (net (code "6") (name "/-U") (class "Default")
      (node (ref "C48") (pin "2") (pinfunction "2_2") (pintype "passive"))
      (node (ref "P2") (pin "22") (pinfunction "S_22") (pintype "passive"))
    )
    (net (code "7") (name "/FORW") (class "Default")
      (node (ref "P1") (pin "A8") (pinfunction "P$2_A8") (pintype "passive"))
      (node (ref "P2") (pin "6") (pinfunction "S_6") (pintype "passive"))
      (node (ref "U22") (pin "13") (pinfunction "I_13") (pintype "input"))
      (node (ref "U23") (pin "10") (pinfunction "1_10") (pintype "passive"))
    )
    (net (code "8") (name "/ID1") (class "Default")
      (node (ref "P2") (pin "19") (pinfunction "S_19") (pintype "passive"))
      (node (ref "U17") (pin "13") (pinfunction "1_13") (pintype "passive"))
      (node (ref "U18") (pin "13") (pinfunction "I_13") (pintype "input"))
      (node (ref "U3") (pin "7") (pinfunction "I1_7") (pintype "input"))
    )
    (net (code "9") (name "/ID2") (class "Default")
      (node (ref "P2") (pin "21") (pinfunction "S_21") (pintype "passive"))
      (node (ref "U17") (pin "14") (pinfunction "1_14") (pintype "passive"))
      (node (ref "U18") (pin "11") (pinfunction "I_11") (pintype "input"))
      (node (ref "U6") (pin "7") (pinfunction "I1_7") (pintype "input"))
    )
    (net (code "10") (name "/ID3") (class "Default")
      (node (ref "P2") (pin "23") (pinfunction "S_23") (pintype "passive"))
      (node (ref "U17") (pin "15") (pinfunction "1_15") (pintype "passive"))
      (node (ref "U18") (pin "9") (pinfunction "I_9") (pintype "input"))
      (node (ref "U9") (pin "7") (pinfunction "I1_7") (pintype "input"))
    )
    (net (code "11") (name "/IMARK") (class "Default")
      (node (ref "P2") (pin "17") (pinfunction "S_17") (pintype "passive"))
      (node (ref "U15") (pin "7") (pinfunction "I1_7") (pintype "input"))
      (node (ref "U17") (pin "1") (pinfunction "1_1") (pintype "passive"))
      (node (ref "U18") (pin "5") (pinfunction "I_5") (pintype "input"))
    )
    (net (code "12") (name "/ITIMING") (class "Default")
      (node (ref "P2") (pin "15") (pinfunction "S_15") (pintype "passive"))
      (node (ref "U12") (pin "7") (pinfunction "I1_7") (pintype "input"))
      (node (ref "U17") (pin "2") (pinfunction "1_2") (pintype "passive"))
      (node (ref "U18") (pin "3") (pinfunction "I_3") (pintype "input"))
    )
    (net (code "13") (name "/LOAD(RED)") (class "Default")
      (node (ref "C46") (pin "1") (pinfunction "1_1") (pintype "passive"))
      (node (ref "P4") (pin "4") (pinfunction "4_4") (pintype "passive"))
      (node (ref "U19") (pin "10") (pinfunction "I1_10") (pintype "input"))
      (node (ref "U19") (pin "9") (pinfunction "I0_9") (pintype "input"))
      (node (ref "U20") (pin "3") (pinfunction "I0_3") (pintype "input"))
      (node (ref "U23") (pin "9") (pinfunction "1_9") (pintype "passive"))
    )
    (net (code "14") (name "/OD1") (class "Default")
      (node (ref "P2") (pin "9") (pinfunction "S_9") (pintype "passive"))
      (node (ref "U16") (pin "12") (pinfunction "O_12") (pintype "open_collector"))
    )
    (net (code "15") (name "/OD2") (class "Default")
      (node (ref "P2") (pin "11") (pinfunction "S_11") (pintype "passive"))
      (node (ref "U16") (pin "6") (pinfunction "O_6") (pintype "open_collector"))
    )
    (net (code "16") (name "/OD3") (class "Default")
      (node (ref "P2") (pin "13") (pinfunction "S_13") (pintype "passive"))
      (node (ref "U16") (pin "4") (pinfunction "O_4") (pintype "open_collector"))
    )
    (net (code "17") (name "/OMARK") (class "Default")
      (node (ref "P2") (pin "7") (pinfunction "S_7") (pintype "passive"))
      (node (ref "U16") (pin "10") (pinfunction "O_10") (pintype "open_collector"))
    )
    (net (code "18") (name "/ONLINE") (class "Default")
      (node (ref "C47") (pin "1") (pinfunction "1_1") (pintype "passive"))
      (node (ref "U19") (pin "1") (pinfunction "I0_1") (pintype "input"))
      (node (ref "U20") (pin "5") (pinfunction "I2_5") (pintype "input"))
      (node (ref "U20") (pin "8") (pinfunction "O_8") (pintype "output"))
      (node (ref "U24") (pin "10") (pinfunction "I1_10") (pintype "input"))
      (node (ref "U24") (pin "12") (pinfunction "I0_12") (pintype "input"))
    )
    (net (code "19") (name "/OTIMING") (class "Default")
      (node (ref "P2") (pin "5") (pinfunction "S_5") (pintype "passive"))
      (node (ref "U16") (pin "8") (pinfunction "O_8") (pintype "open_collector"))
    )
    (net (code "20") (name "/PWR(BLUE)") (class "Default")
      (node (ref "C44") (pin "1") (pinfunction "1_1") (pintype "passive"))
      (node (ref "P4") (pin "3") (pinfunction "3_3") (pintype "passive"))
      (node (ref "U23") (pin "1") (pinfunction "1_1") (pintype "passive"))
      (node (ref "U24") (pin "4") (pinfunction "I0_4") (pintype "input"))
    )
    (net (code "21") (name "/REV") (class "Default")
      (node (ref "P1") (pin "B8") (pinfunction "P$2_B8") (pintype "passive"))
      (node (ref "P2") (pin "8") (pinfunction "S_8") (pintype "passive"))
      (node (ref "U22") (pin "11") (pinfunction "I_11") (pintype "input"))
      (node (ref "U23") (pin "12") (pinfunction "1_12") (pintype "passive"))
    )
    (net (code "22") (name "/REW(ORANGE)") (class "Default")
      (node (ref "C43") (pin "1") (pinfunction "1_1") (pintype "passive"))
      (node (ref "P4") (pin "5") (pinfunction "5_5") (pintype "passive"))
      (node (ref "U19") (pin "13") (pinfunction "I2_13") (pintype "input"))
      (node (ref "U20") (pin "11") (pinfunction "I2_11") (pintype "input"))
      (node (ref "U20") (pin "13") (pinfunction "I2_13") (pintype "input"))
      (node (ref "U23") (pin "15") (pinfunction "1_15") (pintype "passive"))
    )
    (net (code "23") (name "/S0") (class "Default")
      (node (ref "P1") (pin "A6") (pinfunction "P$2_A6") (pintype "passive"))
      (node (ref "P2") (pin "14") (pinfunction "S_14") (pintype "passive"))
      (node (ref "U21") (pin "1") (pinfunction "I_1") (pintype "input"))
      (node (ref "U23") (pin "6") (pinfunction "1_6") (pintype "passive"))
    )
    (net (code "24") (name "/S1") (class "Default")
      (node (ref "P1") (pin "B6") (pinfunction "P$2_B6") (pintype "passive"))
      (node (ref "P2") (pin "16") (pinfunction "S_16") (pintype "passive"))
      (node (ref "U21") (pin "3") (pinfunction "I_3") (pintype "input"))
      (node (ref "U23") (pin "4") (pinfunction "1_4") (pintype "passive"))
    )
    (net (code "25") (name "/SELECTED") (class "Default")
      (node (ref "1") (pin "1") (pinfunction "P_1") (pintype "passive"))
      (node (ref "2") (pin "1") (pinfunction "P_1") (pintype "passive"))
      (node (ref "4") (pin "1") (pinfunction "P_1") (pintype "passive"))
      (node (ref "5") (pin "1") (pinfunction "P_1") (pintype "passive"))
      (node (ref "C37") (pin "1") (pinfunction "1_1") (pintype "passive"))
      (node (ref "U19") (pin "3") (pinfunction "I0_3") (pintype "input"))
      (node (ref "U19") (pin "4") (pinfunction "I1_4") (pintype "input"))
      (node (ref "U20") (pin "2") (pinfunction "I1_2") (pintype "input"))
      (node (ref "U21") (pin "10") (pinfunction "O_10") (pintype "open_collector"))
      (node (ref "U21") (pin "12") (pinfunction "O_12") (pintype "open_collector"))
      (node (ref "U22") (pin "9") (pinfunction "I_9") (pintype "input"))
      (node (ref "U23") (pin "14") (pinfunction "1_14") (pintype "passive"))
      (node (ref "U24") (pin "13") (pinfunction "I1_13") (pintype "input"))
    )
    (net (code "26") (name "/WE(YELLOW)") (class "Default")
      (node (ref "C45") (pin "1") (pinfunction "1_1") (pintype "passive"))
      (node (ref "P4") (pin "2") (pinfunction "2_2") (pintype "passive"))
      (node (ref "U23") (pin "2") (pinfunction "1_2") (pintype "passive"))
      (node (ref "U24") (pin "1") (pinfunction "I0_1") (pintype "input"))
    )
    (net (code "27") (name "/~{DS}") (class "Default")
      (node (ref "P1") (pin "B7") (pinfunction "P$2_B7") (pintype "passive"))
      (node (ref "P2") (pin "12") (pinfunction "S_12") (pintype "passive"))
      (node (ref "U21") (pin "8") (pinfunction "O_8") (pintype "open_collector"))
    )
    (net (code "28") (name "/~{IFE}") (class "Default")
      (node (ref "12") (pin "1") (pinfunction "P_1") (pintype "passive"))
      (node (ref "13") (pin "1") (pinfunction "P_1") (pintype "passive"))
      (node (ref "P2") (pin "20") (pinfunction "S_20") (pintype "passive"))
      (node (ref "U17") (pin "4") (pinfunction "1_4") (pintype "passive"))
      (node (ref "U22") (pin "5") (pinfunction "I_5") (pintype "input"))
    )
    (net (code "29") (name "/~{IWE}") (class "Default")
      (node (ref "10") (pin "1") (pinfunction "P_1") (pintype "passive"))
      (node (ref "11") (pin "1") (pinfunction "P_1") (pintype "passive"))
      (node (ref "P2") (pin "18") (pinfunction "S_18") (pintype "passive"))
      (node (ref "U17") (pin "3") (pinfunction "1_3") (pintype "passive"))
      (node (ref "U18") (pin "1") (pinfunction "I_1") (pintype "input"))
    )
    (net (code "30") (name "/~{WE}") (class "Default")
      (node (ref "P1") (pin "A7") (pinfunction "P$2_A7") (pintype "passive"))
      (node (ref "P2") (pin "10") (pinfunction "S_10") (pintype "passive"))
      (node (ref "U21") (pin "6") (pinfunction "O_6") (pintype "open_collector"))
    )
    (net (code "31") (name "GND") (class "Default")
      (node (ref "C31") (pin "1") (pinfunction "1_1") (pintype "passive"))
      (node (ref "C32") (pin "2") (pinfunction "2_2") (pintype "passive"))
      (node (ref "C34") (pin "-") (pinfunction "-_-") (pintype "passive"))
      (node (ref "C35") (pin "2") (pinfunction "2_2") (pintype "passive"))
      (node (ref "C37") (pin "2") (pinfunction "2_2") (pintype "passive"))
      (node (ref "C40") (pin "1") (pinfunction "1_1") (pintype "passive"))
      (node (ref "C40") (pin "2") (pinfunction "2_2") (pintype "passive"))
      (node (ref "C41") (pin "-") (pinfunction "-_-") (pintype "passive"))
      (node (ref "C42") (pin "2") (pinfunction "2_2") (pintype "passive"))
      (node (ref "C43") (pin "2") (pinfunction "2_2") (pintype "passive"))
      (node (ref "C44") (pin "2") (pinfunction "2_2") (pintype "passive"))
      (node (ref "C45") (pin "2") (pinfunction "2_2") (pintype "passive"))
      (node (ref "C46") (pin "2") (pinfunction "2_2") (pintype "passive"))
      (node (ref "C47") (pin "2") (pinfunction "2_2") (pintype "passive"))
      (node (ref "C49") (pin "2") (pinfunction "2_2") (pintype "passive"))
      (node (ref "C50") (pin "2") (pinfunction "2_2") (pintype "passive"))
      (node (ref "C51") (pin "+") (pinfunction "+_+") (pintype "passive"))
      (node (ref "C53") (pin "+") (pinfunction "+_+") (pintype "passive"))
      (node (ref "CR11") (pin "A") (pinfunction "A_A") (pintype "passive"))
      (node (ref "CR34") (pin "A") (pinfunction "A_A") (pintype "passive"))
      (node (ref "CT7") (pin "-") (pinfunction "-_-") (pintype "passive"))
      (node (ref "GND") (pin "1") (pinfunction "1_1") (pintype "passive"))
      (node (ref "J1") (pin "1") (pinfunction "1_1") (pintype "passive"))
      (node (ref "J1") (pin "2") (pinfunction "2_2") (pintype "passive"))
      (node (ref "P1") (pin "A11") (pinfunction "P$2_A11") (pintype "passive"))
      (node (ref "P1") (pin "A13") (pinfunction "P$2_A13") (pintype "passive"))
      (node (ref "P1") (pin "B13") (pinfunction "P$2_B13") (pintype "passive"))
      (node (ref "P2") (pin "1") (pinfunction "S_1") (pintype "passive"))
      (node (ref "P2") (pin "2") (pinfunction "S_2") (pintype "passive"))
      (node (ref "P2") (pin "26") (pinfunction "S_26") (pintype "passive"))
      (node (ref "P4") (pin "1") (pinfunction "1_1") (pintype "passive"))
      (node (ref "P5") (pin "3") (pinfunction "3_3") (pintype "passive"))
      (node (ref "PAD4") (pin "1") (pinfunction "P_1") (pintype "passive"))
      (node (ref "Q5") (pin "1") (pinfunction "E_1") (pintype "passive"))
      (node (ref "R10") (pin "2") (pinfunction "2_2") (pintype "passive"))
      (node (ref "R11") (pin "2") (pinfunction "2_2") (pintype "passive"))
      (node (ref "R12") (pin "2") (pinfunction "2_2") (pintype "passive"))
      (node (ref "R18") (pin "1") (pinfunction "1_1") (pintype "passive"))
      (node (ref "R20") (pin "2") (pinfunction "2_2") (pintype "passive"))
      (node (ref "R22") (pin "2") (pinfunction "2_2") (pintype "passive"))
      (node (ref "R24") (pin "2") (pinfunction "2_2") (pintype "passive"))
      (node (ref "R25") (pin "2") (pinfunction "2_2") (pintype "passive"))
      (node (ref "R26") (pin "2") (pinfunction "2_2") (pintype "passive"))
      (node (ref "R32") (pin "1") (pinfunction "1_1") (pintype "passive"))
      (node (ref "R34") (pin "2") (pinfunction "2_2") (pintype "passive"))
      (node (ref "R36") (pin "2") (pinfunction "2_2") (pintype "passive"))
      (node (ref "R38") (pin "2") (pinfunction "2_2") (pintype "passive"))
      (node (ref "R39") (pin "2") (pinfunction "2_2") (pintype "passive"))
      (node (ref "R4") (pin "1") (pinfunction "1_1") (pintype "passive"))
      (node (ref "R40") (pin "2") (pinfunction "2_2") (pintype "passive"))
      (node (ref "R46") (pin "1") (pinfunction "1_1") (pintype "passive"))
      (node (ref "R48") (pin "2") (pinfunction "2_2") (pintype "passive"))
      (node (ref "R50") (pin "2") (pinfunction "2_2") (pintype "passive"))
      (node (ref "R52") (pin "2") (pinfunction "2_2") (pintype "passive"))
      (node (ref "R53") (pin "2") (pinfunction "2_2") (pintype "passive"))
      (node (ref "R54") (pin "2") (pinfunction "2_2") (pintype "passive"))
      (node (ref "R6") (pin "2") (pinfunction "2_2") (pintype "passive"))
      (node (ref "R60") (pin "1") (pinfunction "1_1") (pintype "passive"))
      (node (ref "R62") (pin "2") (pinfunction "2_2") (pintype "passive"))
      (node (ref "R64") (pin "2") (pinfunction "2_2") (pintype "passive"))
      (node (ref "R66") (pin "2") (pinfunction "2_2") (pintype "passive"))
      (node (ref "R67") (pin "2") (pinfunction "2_2") (pintype "passive"))
      (node (ref "R68") (pin "2") (pinfunction "2_2") (pintype "passive"))
      (node (ref "R73") (pin "2") (pinfunction "2_2") (pintype "passive"))
      (node (ref "R75") (pin "2") (pinfunction "2_2") (pintype "passive"))
      (node (ref "R79") (pin "2") (pinfunction "2_2") (pintype "passive"))
      (node (ref "R8") (pin "2") (pinfunction "2_2") (pintype "passive"))
      (node (ref "R83") (pin "1") (pinfunction "1_1") (pintype "passive"))
      (node (ref "R84") (pin "1") (pinfunction "1_1") (pintype "passive"))
      (node (ref "U25") (pin "1") (pinfunction "A1_1") (pintype "input"))
      (node (ref "U25") (pin "2") (pinfunction "A2_2") (pintype "input"))
      (node (ref "U26") (pin "2") (pinfunction "GND_2") (pintype "passive"))
    )
    (net (code "32") (name "Net-(3-P)") (class "Default")
      (node (ref "3") (pin "1") (pinfunction "P_1") (pintype "passive"))
      (node (ref "U21") (pin "13") (pinfunction "I_13") (pintype "input"))
      (node (ref "U21") (pin "2") (pinfunction "O_2") (pintype "open_collector"))
      (node (ref "U23") (pin "5") (pinfunction "1_5") (pintype "passive"))
    )
    (net (code "33") (name "Net-(6-P)") (class "Default")
      (node (ref "6") (pin "1") (pinfunction "P_1") (pintype "passive"))
      (node (ref "U21") (pin "11") (pinfunction "I_11") (pintype "input"))
      (node (ref "U21") (pin "4") (pinfunction "O_4") (pintype "open_collector"))
      (node (ref "U23") (pin "3") (pinfunction "1_3") (pintype "passive"))
    )
    (net (code "34") (name "Net-(7-P)") (class "Default")
      (node (ref "7") (pin "1") (pinfunction "P_1") (pintype "passive"))
      (node (ref "8") (pin "1") (pinfunction "P_1") (pintype "passive"))
      (node (ref "C50") (pin "1") (pinfunction "1_1") (pintype "passive"))
      (node (ref "P1") (pin "B9") (pinfunction "P$2_B9") (pintype "passive"))
      (node (ref "U16") (pin "2") (pinfunction "O_2") (pintype "open_collector"))
      (node (ref "U23") (pin "8") (pinfunction "1_8") (pintype "passive"))
      (node (ref "U24") (pin "5") (pinfunction "I1_5") (pintype "input"))
    )
    (net (code "35") (name "Net-(9-P)") (class "Default")
      (node (ref "9") (pin "1") (pinfunction "P_1") (pintype "passive"))
      (node (ref "CR31") (pin "C") (pinfunction "C_C") (pintype "passive"))
      (node (ref "U20") (pin "10") (pinfunction "I1_10") (pintype "input"))
      (node (ref "U23") (pin "7") (pinfunction "1_7") (pintype "passive"))
    )
    (net (code "36") (name "Net-(C2-Pad2)") (class "Default")
      (node (ref "C2") (pin "2") (pinfunction "2_2") (pintype "passive"))
      (node (ref "R5") (pin "1") (pinfunction "1_1") (pintype "passive"))
      (node (ref "R6") (pin "1") (pinfunction "1_1") (pintype "passive"))
    )
    (net (code "37") (name "Net-(C3-Pad2)") (class "Default")
      (node (ref "C3") (pin "2") (pinfunction "2_2") (pintype "passive"))
      (node (ref "R3") (pin "1") (pinfunction "1_1") (pintype "passive"))
      (node (ref "R4") (pin "2") (pinfunction "2_2") (pintype "passive"))
    )
    (net (code "38") (name "Net-(C5-Pad2)") (class "Default")
      (node (ref "C5") (pin "2") (pinfunction "2_2") (pintype "passive"))
      (node (ref "R10") (pin "1") (pinfunction "1_1") (pintype "passive"))
      (node (ref "R9") (pin "1") (pinfunction "1_1") (pintype "passive"))
    )
    (net (code "39") (name "Net-(C6-Pad2)") (class "Default")
      (node (ref "C6") (pin "2") (pinfunction "2_2") (pintype "passive"))
      (node (ref "R7") (pin "1") (pinfunction "1_1") (pintype "passive"))
      (node (ref "R8") (pin "1") (pinfunction "1_1") (pintype "passive"))
    )
    (net (code "40") (name "Net-(C8-Pad2)") (class "Default")
      (node (ref "C8") (pin "2") (pinfunction "2_2") (pintype "passive"))
      (node (ref "R19") (pin "1") (pinfunction "1_1") (pintype "passive"))
      (node (ref "R20") (pin "1") (pinfunction "1_1") (pintype "passive"))
    )
    (net (code "41") (name "Net-(C9-Pad2)") (class "Default")
      (node (ref "C9") (pin "2") (pinfunction "2_2") (pintype "passive"))
      (node (ref "R17") (pin "1") (pinfunction "1_1") (pintype "passive"))
      (node (ref "R18") (pin "2") (pinfunction "2_2") (pintype "passive"))
    )
    (net (code "42") (name "Net-(C11-Pad2)") (class "Default")
      (node (ref "C11") (pin "2") (pinfunction "2_2") (pintype "passive"))
      (node (ref "R23") (pin "1") (pinfunction "1_1") (pintype "passive"))
      (node (ref "R24") (pin "1") (pinfunction "1_1") (pintype "passive"))
    )
    (net (code "43") (name "Net-(C12-Pad2)") (class "Default")
      (node (ref "C12") (pin "2") (pinfunction "2_2") (pintype "passive"))
      (node (ref "R21") (pin "1") (pinfunction "1_1") (pintype "passive"))
      (node (ref "R22") (pin "1") (pinfunction "1_1") (pintype "passive"))
    )
    (net (code "44") (name "Net-(C14-Pad2)") (class "Default")
      (node (ref "C14") (pin "2") (pinfunction "2_2") (pintype "passive"))
      (node (ref "R33") (pin "1") (pinfunction "1_1") (pintype "passive"))
      (node (ref "R34") (pin "1") (pinfunction "1_1") (pintype "passive"))
    )
    (net (code "45") (name "Net-(C15-Pad2)") (class "Default")
      (node (ref "C15") (pin "2") (pinfunction "2_2") (pintype "passive"))
      (node (ref "R31") (pin "1") (pinfunction "1_1") (pintype "passive"))
      (node (ref "R32") (pin "2") (pinfunction "2_2") (pintype "passive"))
    )
    (net (code "46") (name "Net-(C17-Pad2)") (class "Default")
      (node (ref "C17") (pin "2") (pinfunction "2_2") (pintype "passive"))
      (node (ref "R37") (pin "1") (pinfunction "1_1") (pintype "passive"))
      (node (ref "R38") (pin "1") (pinfunction "1_1") (pintype "passive"))
    )
    (net (code "47") (name "Net-(C18-Pad2)") (class "Default")
      (node (ref "C18") (pin "2") (pinfunction "2_2") (pintype "passive"))
      (node (ref "R35") (pin "1") (pinfunction "1_1") (pintype "passive"))
      (node (ref "R36") (pin "1") (pinfunction "1_1") (pintype "passive"))
    )
    (net (code "48") (name "Net-(C20-Pad2)") (class "Default")
      (node (ref "C20") (pin "2") (pinfunction "2_2") (pintype "passive"))
      (node (ref "R47") (pin "1") (pinfunction "1_1") (pintype "passive"))
      (node (ref "R48") (pin "1") (pinfunction "1_1") (pintype "passive"))
    )
    (net (code "49") (name "Net-(C21-Pad2)") (class "Default")
      (node (ref "C21") (pin "2") (pinfunction "2_2") (pintype "passive"))
      (node (ref "R45") (pin "1") (pinfunction "1_1") (pintype "passive"))
      (node (ref "R46") (pin "2") (pinfunction "2_2") (pintype "passive"))
    )
    (net (code "50") (name "Net-(C23-Pad2)") (class "Default")
      (node (ref "C23") (pin "2") (pinfunction "2_2") (pintype "passive"))
      (node (ref "R51") (pin "1") (pinfunction "1_1") (pintype "passive"))
      (node (ref "R52") (pin "1") (pinfunction "1_1") (pintype "passive"))
    )
    (net (code "51") (name "Net-(C24-Pad2)") (class "Default")
      (node (ref "C24") (pin "2") (pinfunction "2_2") (pintype "passive"))
      (node (ref "R49") (pin "1") (pinfunction "1_1") (pintype "passive"))
      (node (ref "R50") (pin "1") (pinfunction "1_1") (pintype "passive"))
    )
    (net (code "52") (name "Net-(C26-Pad2)") (class "Default")
      (node (ref "C26") (pin "2") (pinfunction "2_2") (pintype "passive"))
      (node (ref "R61") (pin "1") (pinfunction "1_1") (pintype "passive"))
      (node (ref "R62") (pin "1") (pinfunction "1_1") (pintype "passive"))
    )
    (net (code "53") (name "Net-(C27-Pad2)") (class "Default")
      (node (ref "C27") (pin "2") (pinfunction "2_2") (pintype "passive"))
      (node (ref "R59") (pin "1") (pinfunction "1_1") (pintype "passive"))
      (node (ref "R60") (pin "2") (pinfunction "2_2") (pintype "passive"))
    )
    (net (code "54") (name "Net-(C29-Pad2)") (class "Default")
      (node (ref "C29") (pin "2") (pinfunction "2_2") (pintype "passive"))
      (node (ref "R65") (pin "1") (pinfunction "1_1") (pintype "passive"))
      (node (ref "R66") (pin "1") (pinfunction "1_1") (pintype "passive"))
    )
    (net (code "55") (name "Net-(C30-Pad2)") (class "Default")
      (node (ref "C30") (pin "2") (pinfunction "2_2") (pintype "passive"))
      (node (ref "R63") (pin "1") (pinfunction "1_1") (pintype "passive"))
      (node (ref "R64") (pin "1") (pinfunction "1_1") (pintype "passive"))
    )
    (net (code "56") (name "Net-(C38-Pad2)") (class "Default")
      (node (ref "C38") (pin "2") (pinfunction "2_2") (pintype "passive"))
      (node (ref "R85") (pin "1") (pinfunction "1_1") (pintype "passive"))
    )
    (net (code "57") (name "Net-(C39-Pad1)") (class "Default")
      (node (ref "C39") (pin "1") (pinfunction "1_1") (pintype "passive"))
      (node (ref "R89") (pin "2") (pinfunction "2_2") (pintype "passive"))
    )
    (net (code "58") (name "Net-(C48-Pad1)") (class "Default")
      (node (ref "C48") (pin "1") (pinfunction "1_1") (pintype "passive"))
      (node (ref "R91") (pin "2") (pinfunction "2_2") (pintype "passive"))
    )
    (net (code "59") (name "Net-(C51-Pad-)") (class "Default")
      (node (ref "C51") (pin "-") (pinfunction "-_-") (pintype "passive"))
      (node (ref "R90") (pin "2") (pinfunction "2_2") (pintype "passive"))
      (node (ref "R91") (pin "1") (pinfunction "1_1") (pintype "passive"))
    )
    (net (code "60") (name "Net-(CR11-PadC)") (class "Default")
      (node (ref "CR11") (pin "C") (pinfunction "C_C") (pintype "passive"))
      (node (ref "Q1") (pin "B") (pinfunction "B_B") (pintype "passive"))
      (node (ref "R72") (pin "1") (pinfunction "1_1") (pintype "passive"))
    )
    (net (code "61") (name "Net-(CR22-PadA)") (class "Default")
      (node (ref "CR22") (pin "A") (pinfunction "A_A") (pintype "passive"))
      (node (ref "R82") (pin "1") (pinfunction "1_1") (pintype "passive"))
    )
    (net (code "62") (name "Net-(CR23-PadA)") (class "Default")
      (node (ref "CR23") (pin "A") (pinfunction "A_A") (pintype "passive"))
      (node (ref "P5") (pin "4") (pinfunction "4_4") (pintype "passive"))
    )
    (net (code "63") (name "Net-(CR24-PadA)") (class "Default")
      (node (ref "CR24") (pin "A") (pinfunction "A_A") (pintype "passive"))
      (node (ref "CR33") (pin "C") (pinfunction "C_C") (pintype "passive"))
      (node (ref "P5") (pin "2") (pinfunction "2_2") (pintype "passive"))
    )
    (net (code "64") (name "Net-(CR27-PadA)") (class "Default")
      (node (ref "CR27") (pin "A") (pinfunction "A_A") (pintype "passive"))
      (node (ref "CR28") (pin "C") (pinfunction "C_C") (pintype "passive"))
    )
    (net (code "65") (name "Net-(CT1-Pad+)") (class "Default")
      (node (ref "CT1") (pin "+") (pinfunction "+_+") (pintype "passive"))
      (node (ref "R88") (pin "2") (pinfunction "2_2") (pintype "passive"))
    )
    (net (code "66") (name "Net-(K1B-O)") (class "Default")
      (node (ref "CR27") (pin "C") (pinfunction "C_C") (pintype "passive"))
      (node (ref "K1") (pin "5") (pinfunction "O_5") (pintype "passive"))
      (node (ref "R88") (pin "1") (pinfunction "1_1") (pintype "passive"))
    )
    (net (code "67") (name "Net-(K1B-P)") (class "Default")
      (node (ref "K1") (pin "6") (pinfunction "P_6") (pintype "passive"))
      (node (ref "K2") (pin "8") (pinfunction "O_8") (pintype "passive"))
    )
    (net (code "68") (name "Net-(K1B-S)") (class "Default")
      (node (ref "K1") (pin "7") (pinfunction "S_7") (pintype "passive"))
      (node (ref "R86") (pin "1") (pinfunction "1_1") (pintype "passive"))
    )
    (net (code "69") (name "Net-(K1C-O)") (class "Default")
      (node (ref "K1") (pin "8") (pinfunction "O_8") (pintype "passive"))
      (node (ref "R87") (pin "2") (pinfunction "2_2") (pintype "passive"))
    )
    (net (code "70") (name "Net-(K1C-P)") (class "Default")
      (node (ref "C39") (pin "2") (pinfunction "2_2") (pintype "passive"))
      (node (ref "CR28") (pin "A") (pinfunction "A_A") (pintype "passive"))
      (node (ref "CR30") (pin "2") (pinfunction "2_2") (pintype "passive"))
      (node (ref "K1") (pin "9") (pinfunction "P_9") (pintype "passive"))
      (node (ref "K2") (pin "5") (pinfunction "O_5") (pintype "passive"))
      (node (ref "K2") (pin "6") (pinfunction "P_6") (pintype "passive"))
      (node (ref "P7") (pin "1") (pinfunction "1_1") (pintype "passive"))
      (node (ref "P7") (pin "4") (pinfunction "4_4") (pintype "passive"))
    )
    (net (code "71") (name "Net-(K1C-S)") (class "Default")
      (node (ref "CR32") (pin "C") (pinfunction "C_C") (pintype "passive"))
      (node (ref "K1") (pin "10") (pinfunction "S_10") (pintype "passive"))
      (node (ref "K2") (pin "7") (pinfunction "S_7") (pintype "passive"))
      (node (ref "P5") (pin "1") (pinfunction "1_1") (pintype "passive"))
      (node (ref "P8") (pin "3") (pinfunction "3_3") (pintype "passive"))
    )
    (net (code "72") (name "Net-(K2C-P)") (class "Default")
      (node (ref "C38") (pin "1") (pinfunction "1_1") (pintype "passive"))
      (node (ref "CR29") (pin "2") (pinfunction "2_2") (pintype "passive"))
      (node (ref "CR30") (pin "1") (pinfunction "1_1") (pintype "passive"))
      (node (ref "K2") (pin "9") (pinfunction "P_9") (pintype "passive"))
      (node (ref "P6") (pin "5") (pinfunction "5_5") (pintype "passive"))
      (node (ref "P6") (pin "6") (pinfunction "6_6") (pintype "passive"))
      (node (ref "P7") (pin "5") (pinfunction "5_5") (pintype "passive"))
      (node (ref "P7") (pin "6") (pinfunction "6_6") (pintype "passive"))
      (node (ref "R87") (pin "1") (pinfunction "1_1") (pintype "passive"))
      (node (ref "R89") (pin "1") (pinfunction "1_1") (pintype "passive"))
    )
    (net (code "73") (name "Net-(P1A-P$2)") (class "Default")
      (node (ref "C23") (pin "1") (pinfunction "1_1") (pintype "passive"))
      (node (ref "CR12") (pin "C") (pinfunction "C_C") (pintype "passive"))
      (node (ref "P1") (pin "A1") (pinfunction "P$2_A1") (pintype "passive"))
      (node (ref "R53") (pin "1") (pinfunction "1_1") (pintype "passive"))
      (node (ref "R55") (pin "2") (pinfunction "2_2") (pintype "passive"))
    )
    (net (code "74") (name "Net-(P1F-P$2)") (class "Default")
      (node (ref "C29") (pin "1") (pinfunction "1_1") (pintype "passive"))
      (node (ref "CR13") (pin "C") (pinfunction "C_C") (pintype "passive"))
      (node (ref "P1") (pin "A2") (pinfunction "P$2_A2") (pintype "passive"))
      (node (ref "R67") (pin "1") (pinfunction "1_1") (pintype "passive"))
      (node (ref "R69") (pin "2") (pinfunction "2_2") (pintype "passive"))
    )
    (net (code "75") (name "Net-(P1G-P$2)") (class "Default")
      (node (ref "C17") (pin "1") (pinfunction "1_1") (pintype "passive"))
      (node (ref "CR14") (pin "C") (pinfunction "C_C") (pintype "passive"))
      (node (ref "P1") (pin "A3") (pinfunction "P$2_A3") (pintype "passive"))
      (node (ref "R39") (pin "1") (pinfunction "1_1") (pintype "passive"))
      (node (ref "R41") (pin "2") (pinfunction "2_2") (pintype "passive"))
    )
    (net (code "76") (name "Net-(P1H-P$2)") (class "Default")
      (node (ref "C11") (pin "1") (pinfunction "1_1") (pintype "passive"))
      (node (ref "CR15") (pin "C") (pinfunction "C_C") (pintype "passive"))
      (node (ref "P1") (pin "A4") (pinfunction "P$2_A4") (pintype "passive"))
      (node (ref "R25") (pin "1") (pinfunction "1_1") (pintype "passive"))
      (node (ref "R27") (pin "2") (pinfunction "2_2") (pintype "passive"))
    )
    (net (code "77") (name "Net-(P1I-P$2)") (class "Default")
      (node (ref "C5") (pin "1") (pinfunction "1_1") (pintype "passive"))
      (node (ref "CR16") (pin "C") (pinfunction "C_C") (pintype "passive"))
      (node (ref "P1") (pin "A5") (pinfunction "P$2_A5") (pintype "passive"))
      (node (ref "R11") (pin "1") (pinfunction "1_1") (pintype "passive"))
      (node (ref "R13") (pin "2") (pinfunction "2_2") (pintype "passive"))
    )
    (net (code "78") (name "Net-(P1N-P$2)") (class "Default")
      (node (ref "C24") (pin "1") (pinfunction "1_1") (pintype "passive"))
      (node (ref "CR21") (pin "C") (pinfunction "C_C") (pintype "passive"))
      (node (ref "P1") (pin "B1") (pinfunction "P$2_B1") (pintype "passive"))
      (node (ref "R54") (pin "1") (pinfunction "1_1") (pintype "passive"))
      (node (ref "R56") (pin "2") (pinfunction "2_2") (pintype "passive"))
    )
    (net (code "79") (name "Net-(P1S-P$2)") (class "Default")
      (node (ref "C30") (pin "1") (pinfunction "1_1") (pintype "passive"))
      (node (ref "CR20") (pin "C") (pinfunction "C_C") (pintype "passive"))
      (node (ref "P1") (pin "B2") (pinfunction "P$2_B2") (pintype "passive"))
      (node (ref "R68") (pin "1") (pinfunction "1_1") (pintype "passive"))
      (node (ref "R70") (pin "2") (pinfunction "2_2") (pintype "passive"))
    )
    (net (code "80") (name "Net-(P1T-P$2)") (class "Default")
      (node (ref "C18") (pin "1") (pinfunction "1_1") (pintype "passive"))
      (node (ref "CR19") (pin "C") (pinfunction "C_C") (pintype "passive"))
      (node (ref "P1") (pin "B3") (pinfunction "P$2_B3") (pintype "passive"))
      (node (ref "R40") (pin "1") (pinfunction "1_1") (pintype "passive"))
      (node (ref "R42") (pin "2") (pinfunction "2_2") (pintype "passive"))
    )
    (net (code "81") (name "Net-(P1U-P$2)") (class "Default")
      (node (ref "C12") (pin "1") (pinfunction "1_1") (pintype "passive"))
      (node (ref "CR18") (pin "C") (pinfunction "C_C") (pintype "passive"))
      (node (ref "P1") (pin "B4") (pinfunction "P$2_B4") (pintype "passive"))
      (node (ref "R26") (pin "1") (pinfunction "1_1") (pintype "passive"))
      (node (ref "R28") (pin "2") (pinfunction "2_2") (pintype "passive"))
    )
    (net (code "82") (name "Net-(P1V-P$2)") (class "Default")
      (node (ref "C6") (pin "1") (pinfunction "1_1") (pintype "passive"))
      (node (ref "CR17") (pin "C") (pinfunction "C_C") (pintype "passive"))
      (node (ref "P1") (pin "B5") (pinfunction "P$2_B5") (pintype "passive"))
      (node (ref "R12") (pin "1") (pinfunction "1_1") (pintype "passive"))
      (node (ref "R14") (pin "2") (pinfunction "2_2") (pintype "passive"))
    )
    (net (code "83") (name "Net-(P3B-S)") (class "Default")
      (node (ref "CR15") (pin "A") (pinfunction "A_A") (pintype "passive"))
      (node (ref "P3") (pin "10") (pinfunction "S_10") (pintype "passive"))
    )
    (net (code "84") (name "Net-(P3C-S)") (class "Default")
      (node (ref "P3") (pin "11") (pinfunction "S_11") (pintype "passive"))
      (node (ref "P3") (pin "13") (pinfunction "S_13") (pintype "passive"))
    )
    (net (code "85") (name "Net-(P3D-S)") (class "Default")
      (node (ref "CR16") (pin "A") (pinfunction "A_A") (pintype "passive"))
      (node (ref "P3") (pin "12") (pinfunction "S_12") (pintype "passive"))
    )
    (net (code "86") (name "Net-(P3F-S)") (class "Default")
      (node (ref "P3") (pin "14") (pinfunction "S_14") (pintype "passive"))
      (node (ref "Q1") (pin "E") (pinfunction "E_E") (pintype "passive"))
      (node (ref "R73") (pin "1") (pinfunction "1_1") (pintype "passive"))
    )
    (net (code "87") (name "Net-(P3G-S)") (class "Default")
      (node (ref "P3") (pin "15") (pinfunction "S_15") (pintype "passive"))
      (node (ref "P3") (pin "17") (pinfunction "S_17") (pintype "passive"))
    )
    (net (code "88") (name "Net-(P3H-S)") (class "Default")
      (node (ref "P3") (pin "16") (pinfunction "S_16") (pintype "passive"))
      (node (ref "Q2") (pin "C") (pinfunction "C_C") (pintype "passive"))
      (node (ref "R72") (pin "2") (pinfunction "2_2") (pintype "passive"))
      (node (ref "R75") (pin "1") (pinfunction "1_1") (pintype "passive"))
    )
    (net (code "89") (name "Net-(P3J-S)") (class "Default")
      (node (ref "CR17") (pin "A") (pinfunction "A_A") (pintype "passive"))
      (node (ref "P3") (pin "18") (pinfunction "S_18") (pintype "passive"))
    )
    (net (code "90") (name "Net-(P3K-S)") (class "Default")
      (node (ref "P3") (pin "19") (pinfunction "S_19") (pintype "passive"))
      (node (ref "P3") (pin "23") (pinfunction "S_23") (pintype "passive"))
    )
    (net (code "91") (name "Net-(P3M-S)") (class "Default")
      (node (ref "CR18") (pin "A") (pinfunction "A_A") (pintype "passive"))
      (node (ref "P3") (pin "20") (pinfunction "S_20") (pintype "passive"))
    )
    (net (code "92") (name "Net-(P3O-S)") (class "Default")
      (node (ref "CR19") (pin "A") (pinfunction "A_A") (pintype "passive"))
      (node (ref "P3") (pin "22") (pinfunction "S_22") (pintype "passive"))
    )
    (net (code "93") (name "Net-(P3Q-S)") (class "Default")
      (node (ref "CR20") (pin "A") (pinfunction "A_A") (pintype "passive"))
      (node (ref "P3") (pin "24") (pinfunction "S_24") (pintype "passive"))
    )
    (net (code "94") (name "Net-(P3S-S)") (class "Default")
      (node (ref "CR21") (pin "A") (pinfunction "A_A") (pintype "passive"))
      (node (ref "P3") (pin "26") (pinfunction "S_26") (pintype "passive"))
    )
    (net (code "95") (name "Net-(P3T-S)") (class "Default")
      (node (ref "P3") (pin "3") (pinfunction "S_3") (pintype "passive"))
      (node (ref "P3") (pin "5") (pinfunction "S_5") (pintype "passive"))
    )
    (net (code "96") (name "Net-(P3U-S)") (class "Default")
      (node (ref "CR12") (pin "A") (pinfunction "A_A") (pintype "passive"))
      (node (ref "P3") (pin "4") (pinfunction "S_4") (pintype "passive"))
    )
    (net (code "97") (name "Net-(P3W-S)") (class "Default")
      (node (ref "CR13") (pin "A") (pinfunction "A_A") (pintype "passive"))
      (node (ref "P3") (pin "6") (pinfunction "S_6") (pintype "passive"))
    )
    (net (code "98") (name "Net-(P3X-S)") (class "Default")
      (node (ref "P3") (pin "7") (pinfunction "S_7") (pintype "passive"))
      (node (ref "P3") (pin "9") (pinfunction "S_9") (pintype "passive"))
    )
    (net (code "99") (name "Net-(P3Y-S)") (class "Default")
      (node (ref "CR14") (pin "A") (pinfunction "A_A") (pintype "passive"))
      (node (ref "P3") (pin "8") (pinfunction "S_8") (pintype "passive"))
    )
    (net (code "100") (name "Net-(P6-Pad2)") (class "Default")
      (node (ref "P6") (pin "2") (pinfunction "2_2") (pintype "passive"))
      (node (ref "P6") (pin "3") (pinfunction "3_3") (pintype "passive"))
    )
    (net (code "101") (name "Net-(P7-Pad2)") (class "Default")
      (node (ref "P7") (pin "2") (pinfunction "2_2") (pintype "passive"))
      (node (ref "P7") (pin "3") (pinfunction "3_3") (pintype "passive"))
    )
    (net (code "102") (name "Net-(PAD2-P)") (class "Default")
      (node (ref "CR29") (pin "1") (pinfunction "1_1") (pintype "passive"))
      (node (ref "CT1") (pin "-") (pinfunction "-_-") (pintype "passive"))
      (node (ref "P5") (pin "5") (pinfunction "5_5") (pintype "passive"))
      (node (ref "P6") (pin "1") (pinfunction "1_1") (pintype "passive"))
      (node (ref "P6") (pin "4") (pinfunction "4_4") (pintype "passive"))
      (node (ref "P8") (pin "1") (pinfunction "1_1") (pintype "passive"))
      (node (ref "PAD2") (pin "1") (pinfunction "P_1") (pintype "passive"))
      (node (ref "R85") (pin "2") (pinfunction "2_2") (pintype "passive"))
      (node (ref "R86") (pin "2") (pinfunction "2_2") (pintype "passive"))
    )
    (net (code "103") (name "Net-(PAD3-P)") (class "Default")
      (node (ref "C52") (pin "2") (pinfunction "2_2") (pintype "passive"))
      (node (ref "C53") (pin "-") (pinfunction "-_-") (pintype "passive"))
      (node (ref "PAD3") (pin "1") (pinfunction "P_1") (pintype "passive"))
      (node (ref "R90") (pin "1") (pinfunction "1_1") (pintype "passive"))
      (node (ref "U27") (pin "2") (pinfunction "VI_2") (pintype "input"))
    )
    (net (code "104") (name "Net-(Q2-PadB)") (class "Default")
      (node (ref "Q2") (pin "B") (pinfunction "B_B") (pintype "passive"))
      (node (ref "R74") (pin "2") (pinfunction "2_2") (pintype "passive"))
      (node (ref "R76") (pin "2") (pinfunction "2_2") (pintype "passive"))
    )
    (net (code "105") (name "Net-(Q3-PadB)") (class "Default")
      (node (ref "Q3") (pin "B") (pinfunction "B_B") (pintype "passive"))
      (node (ref "R80") (pin "1") (pinfunction "1_1") (pintype "passive"))
      (node (ref "R81") (pin "2") (pinfunction "2_2") (pintype "passive"))
    )
    (net (code "106") (name "Net-(Q4-B)") (class "Default")
      (node (ref "Q4") (pin "2") (pinfunction "B_2") (pintype "passive"))
      (node (ref "R82") (pin "2") (pinfunction "2_2") (pintype "passive"))
      (node (ref "R83") (pin "2") (pinfunction "2_2") (pintype "passive"))
    )
    (net (code "107") (name "Net-(Q4-C)") (class "Default")
      (node (ref "Q4") (pin "3") (pinfunction "C_3") (pintype "passive"))
      (node (ref "Q5") (pin "3") (pinfunction "C_3") (pintype "passive"))
      (node (ref "R81") (pin "1") (pinfunction "1_1") (pintype "passive"))
    )
    (net (code "108") (name "Net-(Q4-E)") (class "Default")
      (node (ref "Q4") (pin "1") (pinfunction "E_1") (pintype "passive"))
      (node (ref "Q5") (pin "2") (pinfunction "B_2") (pintype "passive"))
    )
    (net (code "109") (name "Net-(U1E-+IN)") (class "Default")
      (node (ref "C1") (pin "1") (pinfunction "1_1") (pintype "passive"))
      (node (ref "R2") (pin "1") (pinfunction "1_1") (pintype "passive"))
      (node (ref "R3") (pin "2") (pinfunction "2_2") (pintype "passive"))
      (node (ref "U1") (pin "1") (pinfunction "+IN_1") (pintype "input"))
    )
    (net (code "110") (name "Net-(U1E--IN)") (class "Default")
      (node (ref "C1") (pin "2") (pinfunction "2_2") (pintype "passive"))
      (node (ref "R1") (pin "1") (pinfunction "1_1") (pintype "passive"))
      (node (ref "R5") (pin "2") (pinfunction "2_2") (pintype "passive"))
      (node (ref "U1") (pin "14") (pinfunction "-IN_14") (pintype "input"))
    )
    (net (code "111") (name "Net-(U1E-GA1)") (class "Default")
      (node (ref "U1") (pin "11") (pinfunction "GB1_11") (pintype "passive"))
      (node (ref "U1") (pin "4") (pinfunction "GA1_4") (pintype "passive"))
    )
    (net (code "112") (name "Net-(U1E-OUT+)") (class "Default")
      (node (ref "R2") (pin "2") (pinfunction "2_2") (pintype "passive"))
      (node (ref "U1") (pin "7") (pinfunction "OUT+_7") (pintype "output"))
    )
    (net (code "113") (name "Net-(U2E-+IN)") (class "Default")
      (node (ref "C4") (pin "1") (pinfunction "1_1") (pintype "passive"))
      (node (ref "CR1") (pin "C") (pinfunction "C_C") (pintype "passive"))
      (node (ref "CR2") (pin "A") (pinfunction "A_A") (pintype "passive"))
      (node (ref "R7") (pin "2") (pinfunction "2_2") (pintype "passive"))
      (node (ref "U2") (pin "1") (pinfunction "+IN_1") (pintype "input"))
    )
    (net (code "114") (name "Net-(U2E--IN)") (class "Default")
      (node (ref "C4") (pin "2") (pinfunction "2_2") (pintype "passive"))
      (node (ref "CR1") (pin "A") (pinfunction "A_A") (pintype "passive"))
      (node (ref "CR2") (pin "C") (pinfunction "C_C") (pintype "passive"))
      (node (ref "R9") (pin "2") (pinfunction "2_2") (pintype "passive"))
      (node (ref "U2") (pin "14") (pinfunction "-IN_14") (pintype "input"))
    )
    (net (code "115") (name "Net-(U2E-GA1)") (class "Default")
      (node (ref "U2") (pin "11") (pinfunction "GB1_11") (pintype "passive"))
      (node (ref "U2") (pin "4") (pinfunction "GA1_4") (pintype "passive"))
    )
    (net (code "116") (name "Net-(U2E-OUT+)") (class "Default")
      (node (ref "C3") (pin "1") (pinfunction "1_1") (pintype "passive"))
      (node (ref "U2") (pin "7") (pinfunction "OUT+_7") (pintype "output"))
    )
    (net (code "117") (name "Net-(U2E-OUT-)") (class "Default")
      (node (ref "C2") (pin "1") (pinfunction "1_1") (pintype "passive"))
      (node (ref "U2") (pin "8") (pinfunction "OUT-_8") (pintype "output"))
    )
    (net (code "118") (name "Net-(U3A-O)") (class "Default")
      (node (ref "R13") (pin "1") (pinfunction "1_1") (pintype "passive"))
      (node (ref "U3") (pin "3") (pinfunction "O_3") (pintype "open_collector"))
    )
    (net (code "119") (name "Net-(U3B-O)") (class "Default")
      (node (ref "R14") (pin "1") (pinfunction "1_1") (pintype "passive"))
      (node (ref "U3") (pin "5") (pinfunction "O_5") (pintype "open_collector"))
    )
    (net (code "120") (name "Net-(U4E-+IN)") (class "Default")
      (node (ref "C7") (pin "1") (pinfunction "1_1") (pintype "passive"))
      (node (ref "R16") (pin "1") (pinfunction "1_1") (pintype "passive"))
      (node (ref "R17") (pin "2") (pinfunction "2_2") (pintype "passive"))
      (node (ref "U4") (pin "1") (pinfunction "+IN_1") (pintype "input"))
    )
    (net (code "121") (name "Net-(U4E--IN)") (class "Default")
      (node (ref "C7") (pin "2") (pinfunction "2_2") (pintype "passive"))
      (node (ref "R15") (pin "1") (pinfunction "1_1") (pintype "passive"))
      (node (ref "R19") (pin "2") (pinfunction "2_2") (pintype "passive"))
      (node (ref "U4") (pin "14") (pinfunction "-IN_14") (pintype "input"))
    )
    (net (code "122") (name "Net-(U4E-GA1)") (class "Default")
      (node (ref "U4") (pin "11") (pinfunction "GB1_11") (pintype "passive"))
      (node (ref "U4") (pin "4") (pinfunction "GA1_4") (pintype "passive"))
    )
    (net (code "123") (name "Net-(U4E-OUT+)") (class "Default")
      (node (ref "R16") (pin "2") (pinfunction "2_2") (pintype "passive"))
      (node (ref "U4") (pin "7") (pinfunction "OUT+_7") (pintype "output"))
    )
    (net (code "124") (name "Net-(U5E-+IN)") (class "Default")
      (node (ref "C10") (pin "1") (pinfunction "1_1") (pintype "passive"))
      (node (ref "CR3") (pin "C") (pinfunction "C_C") (pintype "passive"))
      (node (ref "CR4") (pin "A") (pinfunction "A_A") (pintype "passive"))
      (node (ref "R21") (pin "2") (pinfunction "2_2") (pintype "passive"))
      (node (ref "U5") (pin "1") (pinfunction "+IN_1") (pintype "input"))
    )
    (net (code "125") (name "Net-(U5E--IN)") (class "Default")
      (node (ref "C10") (pin "2") (pinfunction "2_2") (pintype "passive"))
      (node (ref "CR3") (pin "A") (pinfunction "A_A") (pintype "passive"))
      (node (ref "CR4") (pin "C") (pinfunction "C_C") (pintype "passive"))
      (node (ref "R23") (pin "2") (pinfunction "2_2") (pintype "passive"))
      (node (ref "U5") (pin "14") (pinfunction "-IN_14") (pintype "input"))
    )
    (net (code "126") (name "Net-(U5E-GA1)") (class "Default")
      (node (ref "U5") (pin "11") (pinfunction "GB1_11") (pintype "passive"))
      (node (ref "U5") (pin "4") (pinfunction "GA1_4") (pintype "passive"))
    )
    (net (code "127") (name "Net-(U5E-OUT+)") (class "Default")
      (node (ref "C9") (pin "1") (pinfunction "1_1") (pintype "passive"))
      (node (ref "U5") (pin "7") (pinfunction "OUT+_7") (pintype "output"))
    )
    (net (code "128") (name "Net-(U5E-OUT-)") (class "Default")
      (node (ref "C8") (pin "1") (pinfunction "1_1") (pintype "passive"))
      (node (ref "U5") (pin "8") (pinfunction "OUT-_8") (pintype "output"))
    )
    (net (code "129") (name "Net-(U6A-O)") (class "Default")
      (node (ref "R27") (pin "1") (pinfunction "1_1") (pintype "passive"))
      (node (ref "U6") (pin "3") (pinfunction "O_3") (pintype "open_collector"))
    )
    (net (code "130") (name "Net-(U6B-O)") (class "Default")
      (node (ref "R28") (pin "1") (pinfunction "1_1") (pintype "passive"))
      (node (ref "U6") (pin "5") (pinfunction "O_5") (pintype "open_collector"))
    )
    (net (code "131") (name "Net-(U7E-+IN)") (class "Default")
      (node (ref "C13") (pin "1") (pinfunction "1_1") (pintype "passive"))
      (node (ref "R30") (pin "1") (pinfunction "1_1") (pintype "passive"))
      (node (ref "R31") (pin "2") (pinfunction "2_2") (pintype "passive"))
      (node (ref "U7") (pin "1") (pinfunction "+IN_1") (pintype "input"))
    )
    (net (code "132") (name "Net-(U7E--IN)") (class "Default")
      (node (ref "C13") (pin "2") (pinfunction "2_2") (pintype "passive"))
      (node (ref "R29") (pin "1") (pinfunction "1_1") (pintype "passive"))
      (node (ref "R33") (pin "2") (pinfunction "2_2") (pintype "passive"))
      (node (ref "U7") (pin "14") (pinfunction "-IN_14") (pintype "input"))
    )
    (net (code "133") (name "Net-(U7E-GA1)") (class "Default")
      (node (ref "U7") (pin "11") (pinfunction "GB1_11") (pintype "passive"))
      (node (ref "U7") (pin "4") (pinfunction "GA1_4") (pintype "passive"))
    )
    (net (code "134") (name "Net-(U7E-OUT+)") (class "Default")
      (node (ref "R30") (pin "2") (pinfunction "2_2") (pintype "passive"))
      (node (ref "U7") (pin "7") (pinfunction "OUT+_7") (pintype "output"))
    )
    (net (code "135") (name "Net-(U8E-+IN)") (class "Default")
      (node (ref "C16") (pin "1") (pinfunction "1_1") (pintype "passive"))
      (node (ref "CR5") (pin "C") (pinfunction "C_C") (pintype "passive"))
      (node (ref "CR6") (pin "A") (pinfunction "A_A") (pintype "passive"))
      (node (ref "R35") (pin "2") (pinfunction "2_2") (pintype "passive"))
      (node (ref "U8") (pin "1") (pinfunction "+IN_1") (pintype "input"))
    )
    (net (code "136") (name "Net-(U8E--IN)") (class "Default")
      (node (ref "C16") (pin "2") (pinfunction "2_2") (pintype "passive"))
      (node (ref "CR5") (pin "A") (pinfunction "A_A") (pintype "passive"))
      (node (ref "CR6") (pin "C") (pinfunction "C_C") (pintype "passive"))
      (node (ref "R37") (pin "2") (pinfunction "2_2") (pintype "passive"))
      (node (ref "U8") (pin "14") (pinfunction "-IN_14") (pintype "input"))
    )
    (net (code "137") (name "Net-(U8E-GA1)") (class "Default")
      (node (ref "U8") (pin "11") (pinfunction "GB1_11") (pintype "passive"))
      (node (ref "U8") (pin "4") (pinfunction "GA1_4") (pintype "passive"))
    )
    (net (code "138") (name "Net-(U8E-OUT+)") (class "Default")
      (node (ref "C15") (pin "1") (pinfunction "1_1") (pintype "passive"))
      (node (ref "U8") (pin "7") (pinfunction "OUT+_7") (pintype "output"))
    )
    (net (code "139") (name "Net-(U8E-OUT-)") (class "Default")
      (node (ref "C14") (pin "1") (pinfunction "1_1") (pintype "passive"))
      (node (ref "U8") (pin "8") (pinfunction "OUT-_8") (pintype "output"))
    )
    (net (code "140") (name "Net-(U9A-O)") (class "Default")
      (node (ref "R41") (pin "1") (pinfunction "1_1") (pintype "passive"))
      (node (ref "U9") (pin "3") (pinfunction "O_3") (pintype "open_collector"))
    )
    (net (code "141") (name "Net-(U9B-O)") (class "Default")
      (node (ref "R42") (pin "1") (pinfunction "1_1") (pintype "passive"))
      (node (ref "U9") (pin "5") (pinfunction "O_5") (pintype "open_collector"))
    )
    (net (code "142") (name "Net-(U10E-+IN)") (class "Default")
      (node (ref "C19") (pin "1") (pinfunction "1_1") (pintype "passive"))
      (node (ref "R44") (pin "1") (pinfunction "1_1") (pintype "passive"))
      (node (ref "R45") (pin "2") (pinfunction "2_2") (pintype "passive"))
      (node (ref "U10") (pin "1") (pinfunction "+IN_1") (pintype "input"))
    )
    (net (code "143") (name "Net-(U10E--IN)") (class "Default")
      (node (ref "C19") (pin "2") (pinfunction "2_2") (pintype "passive"))
      (node (ref "R43") (pin "1") (pinfunction "1_1") (pintype "passive"))
      (node (ref "R47") (pin "2") (pinfunction "2_2") (pintype "passive"))
      (node (ref "U10") (pin "14") (pinfunction "-IN_14") (pintype "input"))
    )
    (net (code "144") (name "Net-(U10E-GA1)") (class "Default")
      (node (ref "U10") (pin "11") (pinfunction "GB1_11") (pintype "passive"))
      (node (ref "U10") (pin "4") (pinfunction "GA1_4") (pintype "passive"))
    )
    (net (code "145") (name "Net-(U10E-OUT+)") (class "Default")
      (node (ref "R44") (pin "2") (pinfunction "2_2") (pintype "passive"))
      (node (ref "U10") (pin "7") (pinfunction "OUT+_7") (pintype "output"))
    )
    (net (code "146") (name "Net-(U10E-OUT-)") (class "Default")
      (node (ref "R43") (pin "2") (pinfunction "2_2") (pintype "passive"))
      (node (ref "U10") (pin "8") (pinfunction "OUT-_8") (pintype "output"))
      (node (ref "U16") (pin "9") (pinfunction "I_9") (pintype "input"))
    )
    (net (code "147") (name "Net-(U11E-+IN)") (class "Default")
      (node (ref "C22") (pin "1") (pinfunction "1_1") (pintype "passive"))
      (node (ref "CR7") (pin "C") (pinfunction "C_C") (pintype "passive"))
      (node (ref "CR8") (pin "A") (pinfunction "A_A") (pintype "passive"))
      (node (ref "R49") (pin "2") (pinfunction "2_2") (pintype "passive"))
      (node (ref "U11") (pin "1") (pinfunction "+IN_1") (pintype "input"))
    )
    (net (code "148") (name "Net-(U11E--IN)") (class "Default")
      (node (ref "C22") (pin "2") (pinfunction "2_2") (pintype "passive"))
      (node (ref "CR7") (pin "A") (pinfunction "A_A") (pintype "passive"))
      (node (ref "CR8") (pin "C") (pinfunction "C_C") (pintype "passive"))
      (node (ref "R51") (pin "2") (pinfunction "2_2") (pintype "passive"))
      (node (ref "U11") (pin "14") (pinfunction "-IN_14") (pintype "input"))
    )
    (net (code "149") (name "Net-(U11E-GA1)") (class "Default")
      (node (ref "U11") (pin "11") (pinfunction "GB1_11") (pintype "passive"))
      (node (ref "U11") (pin "4") (pinfunction "GA1_4") (pintype "passive"))
    )
    (net (code "150") (name "Net-(U11E-OUT+)") (class "Default")
      (node (ref "C21") (pin "1") (pinfunction "1_1") (pintype "passive"))
      (node (ref "U11") (pin "7") (pinfunction "OUT+_7") (pintype "output"))
    )
    (net (code "151") (name "Net-(U11E-OUT-)") (class "Default")
      (node (ref "C20") (pin "1") (pinfunction "1_1") (pintype "passive"))
      (node (ref "U11") (pin "8") (pinfunction "OUT-_8") (pintype "output"))
    )
    (net (code "152") (name "Net-(U12A-I0)") (class "Default")
      (node (ref "U12") (pin "1") (pinfunction "I0_1") (pintype "input"))
      (node (ref "U18") (pin "4") (pinfunction "O_4") (pintype "output"))
    )
    (net (code "153") (name "Net-(U12A-I1)") (class "Default")
      (node (ref "R71") (pin "2") (pinfunction "2_2") (pintype "passive"))
      (node (ref "U12") (pin "2") (pinfunction "I1_2") (pintype "input"))
      (node (ref "U12") (pin "6") (pinfunction "I0_6") (pintype "input"))
      (node (ref "U15") (pin "2") (pinfunction "I1_2") (pintype "input"))
      (node (ref "U15") (pin "6") (pinfunction "I0_6") (pintype "input"))
      (node (ref "U22") (pin "6") (pinfunction "O_6") (pintype "open_collector"))
    )
    (net (code "154") (name "Net-(U12A-O)") (class "Default")
      (node (ref "R55") (pin "1") (pinfunction "1_1") (pintype "passive"))
      (node (ref "U12") (pin "3") (pinfunction "O_3") (pintype "open_collector"))
    )
    (net (code "155") (name "Net-(U12B-O)") (class "Default")
      (node (ref "R56") (pin "1") (pinfunction "1_1") (pintype "passive"))
      (node (ref "U12") (pin "5") (pinfunction "O_5") (pintype "open_collector"))
    )
    (net (code "156") (name "Net-(U13E-+IN)") (class "Default")
      (node (ref "C25") (pin "1") (pinfunction "1_1") (pintype "passive"))
      (node (ref "R58") (pin "1") (pinfunction "1_1") (pintype "passive"))
      (node (ref "R59") (pin "2") (pinfunction "2_2") (pintype "passive"))
      (node (ref "U13") (pin "1") (pinfunction "+IN_1") (pintype "input"))
    )
    (net (code "157") (name "Net-(U13E--IN)") (class "Default")
      (node (ref "C25") (pin "2") (pinfunction "2_2") (pintype "passive"))
      (node (ref "R57") (pin "1") (pinfunction "1_1") (pintype "passive"))
      (node (ref "R61") (pin "2") (pinfunction "2_2") (pintype "passive"))
      (node (ref "U13") (pin "14") (pinfunction "-IN_14") (pintype "input"))
    )
    (net (code "158") (name "Net-(U13E-GA1)") (class "Default")
      (node (ref "U13") (pin "11") (pinfunction "GB1_11") (pintype "passive"))
      (node (ref "U13") (pin "4") (pinfunction "GA1_4") (pintype "passive"))
    )
    (net (code "159") (name "Net-(U13E-OUT+)") (class "Default")
      (node (ref "R58") (pin "2") (pinfunction "2_2") (pintype "passive"))
      (node (ref "U13") (pin "7") (pinfunction "OUT+_7") (pintype "output"))
    )
    (net (code "160") (name "Net-(U13E-OUT-)") (class "Default")
      (node (ref "R57") (pin "2") (pinfunction "2_2") (pintype "passive"))
      (node (ref "U13") (pin "8") (pinfunction "OUT-_8") (pintype "output"))
      (node (ref "U16") (pin "11") (pinfunction "I_11") (pintype "input"))
    )
    (net (code "161") (name "Net-(U14E-+IN)") (class "Default")
      (node (ref "C28") (pin "1") (pinfunction "1_1") (pintype "passive"))
      (node (ref "CR10") (pin "A") (pinfunction "A_A") (pintype "passive"))
      (node (ref "CR9") (pin "C") (pinfunction "C_C") (pintype "passive"))
      (node (ref "R63") (pin "2") (pinfunction "2_2") (pintype "passive"))
      (node (ref "U14") (pin "1") (pinfunction "+IN_1") (pintype "input"))
    )
    (net (code "162") (name "Net-(U14E--IN)") (class "Default")
      (node (ref "C28") (pin "2") (pinfunction "2_2") (pintype "passive"))
      (node (ref "CR10") (pin "C") (pinfunction "C_C") (pintype "passive"))
      (node (ref "CR9") (pin "A") (pinfunction "A_A") (pintype "passive"))
      (node (ref "R65") (pin "2") (pinfunction "2_2") (pintype "passive"))
      (node (ref "U14") (pin "14") (pinfunction "-IN_14") (pintype "input"))
    )
    (net (code "163") (name "Net-(U14E-GA1)") (class "Default")
      (node (ref "U14") (pin "11") (pinfunction "GB1_11") (pintype "passive"))
      (node (ref "U14") (pin "4") (pinfunction "GA1_4") (pintype "passive"))
    )
    (net (code "164") (name "Net-(U14E-OUT+)") (class "Default")
      (node (ref "C27") (pin "1") (pinfunction "1_1") (pintype "passive"))
      (node (ref "U14") (pin "7") (pinfunction "OUT+_7") (pintype "output"))
    )
    (net (code "165") (name "Net-(U14E-OUT-)") (class "Default")
      (node (ref "C26") (pin "1") (pinfunction "1_1") (pintype "passive"))
      (node (ref "U14") (pin "8") (pinfunction "OUT-_8") (pintype "output"))
    )
    (net (code "166") (name "Net-(U15A-I0)") (class "Default")
      (node (ref "U15") (pin "1") (pinfunction "I0_1") (pintype "input"))
      (node (ref "U18") (pin "6") (pinfunction "O_6") (pintype "output"))
    )
    (net (code "167") (name "Net-(U15A-O)") (class "Default")
      (node (ref "R69") (pin "1") (pinfunction "1_1") (pintype "passive"))
      (node (ref "U15") (pin "3") (pinfunction "O_3") (pintype "open_collector"))
    )
    (net (code "168") (name "Net-(U15B-O)") (class "Default")
      (node (ref "R70") (pin "1") (pinfunction "1_1") (pintype "passive"))
      (node (ref "U15") (pin "5") (pinfunction "O_5") (pintype "open_collector"))
    )
    (net (code "169") (name "Net-(U16A-I)") (class "Default")
      (node (ref "U16") (pin "1") (pinfunction "I_1") (pintype "input"))
      (node (ref "U25") (pin "8") (pinfunction "Q_8") (pintype "output"))
    )
    (net (code "170") (name "Net-(U16B-I)") (class "Default")
      (node (ref "R29") (pin "2") (pinfunction "2_2") (pintype "passive"))
      (node (ref "U16") (pin "3") (pinfunction "I_3") (pintype "input"))
      (node (ref "U7") (pin "8") (pinfunction "OUT-_8") (pintype "output"))
    )
    (net (code "171") (name "Net-(U16C-I)") (class "Default")
      (node (ref "R15") (pin "2") (pinfunction "2_2") (pintype "passive"))
      (node (ref "U16") (pin "5") (pinfunction "I_5") (pintype "input"))
      (node (ref "U4") (pin "8") (pinfunction "OUT-_8") (pintype "output"))
    )
    (net (code "172") (name "Net-(U16F-I)") (class "Default")
      (node (ref "R1") (pin "2") (pinfunction "2_2") (pintype "passive"))
      (node (ref "U1") (pin "8") (pinfunction "OUT-_8") (pintype "output"))
      (node (ref "U16") (pin "13") (pinfunction "I_13") (pintype "input"))
    )
    (net (code "173") (name "Net-(U18A-O)") (class "Default")
      (node (ref "U18") (pin "2") (pinfunction "O_2") (pintype "output"))
      (node (ref "U3") (pin "2") (pinfunction "I1_2") (pintype "input"))
      (node (ref "U3") (pin "6") (pinfunction "I0_6") (pintype "input"))
      (node (ref "U6") (pin "2") (pinfunction "I1_2") (pintype "input"))
      (node (ref "U6") (pin "6") (pinfunction "I0_6") (pintype "input"))
      (node (ref "U9") (pin "2") (pinfunction "I1_2") (pintype "input"))
      (node (ref "U9") (pin "6") (pinfunction "I0_6") (pintype "input"))
    )
    (net (code "174") (name "Net-(U18D-O)") (class "Default")
      (node (ref "U18") (pin "8") (pinfunction "O_8") (pintype "output"))
      (node (ref "U9") (pin "1") (pinfunction "I0_1") (pintype "input"))
    )
    (net (code "175") (name "Net-(U18E-O)") (class "Default")
      (node (ref "U18") (pin "10") (pinfunction "O_10") (pintype "output"))
      (node (ref "U6") (pin "1") (pinfunction "I0_1") (pintype "input"))
    )
    (net (code "176") (name "Net-(U18F-O)") (class "Default")
      (node (ref "U18") (pin "12") (pinfunction "O_12") (pintype "output"))
      (node (ref "U3") (pin "1") (pinfunction "I0_1") (pintype "input"))
    )
    (net (code "177") (name "Net-(U19A-I1)") (class "Default")
      (node (ref "U19") (pin "2") (pinfunction "I1_2") (pintype "input"))
      (node (ref "U19") (pin "6") (pinfunction "O_6") (pintype "output"))
    )
    (net (code "178") (name "Net-(U19A-O)") (class "Default")
      (node (ref "U19") (pin "11") (pinfunction "I2_11") (pintype "input"))
      (node (ref "U19") (pin "12") (pinfunction "O_12") (pintype "output"))
    )
    (net (code "179") (name "Net-(U19B-I2)") (class "Default")
      (node (ref "U19") (pin "5") (pinfunction "I2_5") (pintype "input"))
      (node (ref "U22") (pin "12") (pinfunction "O_12") (pintype "open_collector"))
      (node (ref "U23") (pin "11") (pinfunction "1_11") (pintype "passive"))
    )
    (net (code "180") (name "Net-(U19C-O)") (class "Default")
      (node (ref "U19") (pin "8") (pinfunction "O_8") (pintype "output"))
      (node (ref "U22") (pin "3") (pinfunction "I_3") (pintype "input"))
    )
    (net (code "181") (name "Net-(U20A-I0)") (class "Default")
      (node (ref "U20") (pin "1") (pinfunction "I0_1") (pintype "input"))
      (node (ref "U22") (pin "10") (pinfunction "O_10") (pintype "open_collector"))
      (node (ref "U23") (pin "13") (pinfunction "1_13") (pintype "passive"))
    )
    (net (code "182") (name "Net-(U20A-O)") (class "Default")
      (node (ref "U20") (pin "12") (pinfunction "O_12") (pintype "output"))
      (node (ref "U24") (pin "9") (pinfunction "I0_9") (pintype "input"))
    )
    (net (code "183") (name "Net-(U20B-I1)") (class "Default")
      (node (ref "U20") (pin "4") (pinfunction "I1_4") (pintype "input"))
      (node (ref "U24") (pin "6") (pinfunction "O_6") (pintype "output"))
    )
    (net (code "184") (name "Net-(U20B-O)") (class "Default")
      (node (ref "U20") (pin "6") (pinfunction "O_6") (pintype "output"))
      (node (ref "U20") (pin "9") (pinfunction "I0_9") (pintype "input"))
    )
    (net (code "185") (name "Net-(U21C-I)") (class "Default")
      (node (ref "U21") (pin "5") (pinfunction "I_5") (pintype "input"))
      (node (ref "U24") (pin "3") (pinfunction "O_3") (pintype "output"))
    )
    (net (code "186") (name "Net-(U21D-I)") (class "Default")
      (node (ref "U21") (pin "9") (pinfunction "I_9") (pintype "input"))
      (node (ref "U24") (pin "11") (pinfunction "O_11") (pintype "output"))
    )
    (net (code "187") (name "Net-(U22A-I)") (class "Default")
      (node (ref "U22") (pin "1") (pinfunction "I_1") (pintype "input"))
      (node (ref "U24") (pin "8") (pinfunction "O_8") (pintype "output"))
    )
    (net (code "188") (name "Net-(U22A-O)") (class "Default")
      (node (ref "CR26") (pin "A") (pinfunction "A_A") (pintype "passive"))
      (node (ref "K2") (pin "1") (pinfunction "1_1") (pintype "passive"))
      (node (ref "U22") (pin "2") (pinfunction "O_2") (pintype "open_collector"))
    )
    (net (code "189") (name "Net-(U22B-O)") (class "Default")
      (node (ref "CR25") (pin "A") (pinfunction "A_A") (pintype "passive"))
      (node (ref "K1") (pin "1") (pinfunction "1_1") (pintype "passive"))
      (node (ref "U22") (pin "4") (pinfunction "O_4") (pintype "open_collector"))
    )
    (net (code "190") (name "Net-(U22D-O)") (class "Default")
      (node (ref "R76") (pin "1") (pinfunction "1_1") (pintype "passive"))
      (node (ref "U22") (pin "8") (pinfunction "O_8") (pintype "open_collector"))
    )
    (net (code "191") (name "Net-(U24A-I1)") (class "Default")
      (node (ref "CR31") (pin "A") (pinfunction "A_A") (pintype "passive"))
      (node (ref "U24") (pin "2") (pinfunction "I1_2") (pintype "input"))
    )
    (net (code "192") (name "Net-(U25A-B1)") (class "Default")
      (node (ref "C49") (pin "1") (pinfunction "1_1") (pintype "passive"))
      (node (ref "R78") (pin "2") (pinfunction "2_2") (pintype "passive"))
      (node (ref "R79") (pin "1") (pinfunction "1_1") (pintype "passive"))
      (node (ref "U25") (pin "3") (pinfunction "B1_3") (pintype "input"))
      (node (ref "U25") (pin "4") (pinfunction "B2_4") (pintype "input"))
    )
    (net (code "193") (name "Net-(U25A-C)") (class "Default")
      (node (ref "C36") (pin "1") (pinfunction "1_1") (pintype "passive"))
      (node (ref "U25") (pin "11") (pinfunction "C_11") (pintype "input"))
    )
    (net (code "194") (name "Net-(U25A-CLR)") (class "Default")
      (node (ref "R77") (pin "1") (pinfunction "1_1") (pintype "passive"))
      (node (ref "U25") (pin "5") (pinfunction "CLR_5") (pintype "input"))
    )
    (net (code "195") (name "Net-(U25A-R{slash}C)") (class "Default")
      (node (ref "C36") (pin "2") (pinfunction "2_2") (pintype "passive"))
      (node (ref "U25") (pin "13") (pinfunction "R/C_13") (pintype "input"))
    )
    (net (code "196") (name "Net-(U26-VI)") (class "Default")
      (node (ref "Q3") (pin "C") (pinfunction "C_C") (pintype "passive"))
      (node (ref "U26") (pin "1") (pinfunction "VI_1") (pintype "input"))
    )
    (net (code "197") (name "Net-(U27-GND)") (class "Default")
      (node (ref "C33") (pin "+") (pinfunction "+_+") (pintype "passive"))
      (node (ref "CR34") (pin "C") (pinfunction "C_C") (pintype "passive"))
      (node (ref "U27") (pin "1") (pinfunction "GND_1") (pintype "passive"))
    )
    (net (code "198") (name "VCC") (class "Default")
      (node (ref "C32") (pin "1") (pinfunction "1_1") (pintype "passive"))
      (node (ref "C35") (pin "1") (pinfunction "1_1") (pintype "passive"))
      (node (ref "C41") (pin "+") (pinfunction "+_+") (pintype "passive"))
      (node (ref "C42") (pin "1") (pinfunction "1_1") (pintype "passive"))
      (node (ref "CR22") (pin "C") (pinfunction "C_C") (pintype "passive"))
      (node (ref "P1") (pin "A12") (pinfunction "P$2_A12") (pintype "passive"))
      (node (ref "P1") (pin "B12") (pinfunction "P$2_B12") (pintype "passive"))
      (node (ref "P2") (pin "3") (pinfunction "S_3") (pintype "passive"))
      (node (ref "P2") (pin "4") (pinfunction "S_4") (pintype "passive"))
      (node (ref "R71") (pin "1") (pinfunction "1_1") (pintype "passive"))
      (node (ref "R77") (pin "2") (pinfunction "2_2") (pintype "passive"))
      (node (ref "U1") (pin "10") (pinfunction "V+_10") (pintype "power_in"))
      (node (ref "U1") (pin "13") (pinfunction "P$2_13") (pintype "passive"))
      (node (ref "U1") (pin "2") (pinfunction "P$2_2") (pintype "passive"))
      (node (ref "U10") (pin "10") (pinfunction "V+_10") (pintype "power_in"))
      (node (ref "U10") (pin "13") (pinfunction "P$2_13") (pintype "passive"))
      (node (ref "U10") (pin "2") (pinfunction "P$2_2") (pintype "passive"))
      (node (ref "U11") (pin "10") (pinfunction "V+_10") (pintype "power_in"))
      (node (ref "U11") (pin "13") (pinfunction "P$2_13") (pintype "passive"))
      (node (ref "U11") (pin "2") (pinfunction "P$2_2") (pintype "passive"))
      (node (ref "U13") (pin "10") (pinfunction "V+_10") (pintype "power_in"))
      (node (ref "U13") (pin "13") (pinfunction "P$2_13") (pintype "passive"))
      (node (ref "U13") (pin "2") (pinfunction "P$2_2") (pintype "passive"))
      (node (ref "U14") (pin "10") (pinfunction "V+_10") (pintype "power_in"))
      (node (ref "U14") (pin "13") (pinfunction "P$2_13") (pintype "passive"))
      (node (ref "U14") (pin "2") (pinfunction "P$2_2") (pintype "passive"))
      (node (ref "U17") (pin "16") (pinfunction "2_16") (pintype "passive"))
      (node (ref "U2") (pin "10") (pinfunction "V+_10") (pintype "power_in"))
      (node (ref "U2") (pin "13") (pinfunction "P$2_13") (pintype "passive"))
      (node (ref "U2") (pin "2") (pinfunction "P$2_2") (pintype "passive"))
      (node (ref "U23") (pin "16") (pinfunction "2_16") (pintype "passive"))
      (node (ref "U25") (pin "9") (pinfunction "R_9") (pintype "input"))
      (node (ref "U4") (pin "10") (pinfunction "V+_10") (pintype "power_in"))
      (node (ref "U4") (pin "13") (pinfunction "P$2_13") (pintype "passive"))
      (node (ref "U4") (pin "2") (pinfunction "P$2_2") (pintype "passive"))
      (node (ref "U5") (pin "10") (pinfunction "V+_10") (pintype "power_in"))
      (node (ref "U5") (pin "13") (pinfunction "P$2_13") (pintype "passive"))
      (node (ref "U5") (pin "2") (pinfunction "P$2_2") (pintype "passive"))
      (node (ref "U7") (pin "10") (pinfunction "V+_10") (pintype "power_in"))
      (node (ref "U7") (pin "13") (pinfunction "P$2_13") (pintype "passive"))
      (node (ref "U7") (pin "2") (pinfunction "P$2_2") (pintype "passive"))
      (node (ref "U8") (pin "10") (pinfunction "V+_10") (pintype "power_in"))
      (node (ref "U8") (pin "13") (pinfunction "P$2_13") (pintype "passive"))
      (node (ref "U8") (pin "2") (pinfunction "P$2_2") (pintype "passive"))
    )
    (net (code "199") (name "unconnected-(GND-Pad2)") (class "Default")
      (node (ref "GND") (pin "2") (pinfunction "2_2") (pintype "passive"))
    )
    (net (code "200") (name "unconnected-(K2C-S-Pad10)") (class "Default")
      (node (ref "K2") (pin "10") (pinfunction "S_10") (pintype "passive"))
    )
    (net (code "201") (name "unconnected-(P3A-S-Pad1)") (class "Default")
      (node (ref "P3") (pin "1") (pinfunction "S_1") (pintype "passive"))
    )
    (net (code "202") (name "unconnected-(P3L-S-Pad2)") (class "Default")
      (node (ref "P3") (pin "2") (pinfunction "S_2") (pintype "passive"))
    )
    (net (code "203") (name "unconnected-(P3N-S-Pad21)") (class "Default")
      (node (ref "P3") (pin "21") (pinfunction "S_21") (pintype "passive"))
    )
    (net (code "204") (name "unconnected-(P3R-S-Pad25)") (class "Default")
      (node (ref "P3") (pin "25") (pinfunction "S_25") (pintype "passive"))
    )
    (net (code "205") (name "unconnected-(P8-Pad2)") (class "Default")
      (node (ref "P8") (pin "2") (pinfunction "2_2") (pintype "passive"))
    )
    (net (code "206") (name "unconnected-(U1E-GA2-Pad3)") (class "Default")
      (node (ref "U1") (pin "3") (pinfunction "GA2_3") (pintype "passive"))
    )
    (net (code "207") (name "unconnected-(U1E-GB2-Pad12)") (class "Default")
      (node (ref "U1") (pin "12") (pinfunction "GB2_12") (pintype "passive"))
    )
    (net (code "208") (name "unconnected-(U2E-GA2-Pad3)") (class "Default")
      (node (ref "U2") (pin "3") (pinfunction "GA2_3") (pintype "passive"))
    )
    (net (code "209") (name "unconnected-(U2E-GB2-Pad12)") (class "Default")
      (node (ref "U2") (pin "12") (pinfunction "GB2_12") (pintype "passive"))
    )
    (net (code "210") (name "unconnected-(U4E-GA2-Pad3)") (class "Default")
      (node (ref "U4") (pin "3") (pinfunction "GA2_3") (pintype "passive"))
    )
    (net (code "211") (name "unconnected-(U4E-GB2-Pad12)") (class "Default")
      (node (ref "U4") (pin "12") (pinfunction "GB2_12") (pintype "passive"))
    )
    (net (code "212") (name "unconnected-(U5E-GA2-Pad3)") (class "Default")
      (node (ref "U5") (pin "3") (pinfunction "GA2_3") (pintype "passive"))
    )
    (net (code "213") (name "unconnected-(U5E-GB2-Pad12)") (class "Default")
      (node (ref "U5") (pin "12") (pinfunction "GB2_12") (pintype "passive"))
    )
    (net (code "214") (name "unconnected-(U7E-GA2-Pad3)") (class "Default")
      (node (ref "U7") (pin "3") (pinfunction "GA2_3") (pintype "passive"))
    )
    (net (code "215") (name "unconnected-(U7E-GB2-Pad12)") (class "Default")
      (node (ref "U7") (pin "12") (pinfunction "GB2_12") (pintype "passive"))
    )
    (net (code "216") (name "unconnected-(U8E-GA2-Pad3)") (class "Default")
      (node (ref "U8") (pin "3") (pinfunction "GA2_3") (pintype "passive"))
    )
    (net (code "217") (name "unconnected-(U8E-GB2-Pad12)") (class "Default")
      (node (ref "U8") (pin "12") (pinfunction "GB2_12") (pintype "passive"))
    )
    (net (code "218") (name "unconnected-(U10E-GA2-Pad3)") (class "Default")
      (node (ref "U10") (pin "3") (pinfunction "GA2_3") (pintype "passive"))
    )
    (net (code "219") (name "unconnected-(U10E-GB2-Pad12)") (class "Default")
      (node (ref "U10") (pin "12") (pinfunction "GB2_12") (pintype "passive"))
    )
    (net (code "220") (name "unconnected-(U11E-GA2-Pad3)") (class "Default")
      (node (ref "U11") (pin "3") (pinfunction "GA2_3") (pintype "passive"))
    )
    (net (code "221") (name "unconnected-(U11E-GB2-Pad12)") (class "Default")
      (node (ref "U11") (pin "12") (pinfunction "GB2_12") (pintype "passive"))
    )
    (net (code "222") (name "unconnected-(U13E-GA2-Pad3)") (class "Default")
      (node (ref "U13") (pin "3") (pinfunction "GA2_3") (pintype "passive"))
    )
    (net (code "223") (name "unconnected-(U13E-GB2-Pad12)") (class "Default")
      (node (ref "U13") (pin "12") (pinfunction "GB2_12") (pintype "passive"))
    )
    (net (code "224") (name "unconnected-(U14E-GA2-Pad3)") (class "Default")
      (node (ref "U14") (pin "3") (pinfunction "GA2_3") (pintype "passive"))
    )
    (net (code "225") (name "unconnected-(U14E-GB2-Pad12)") (class "Default")
      (node (ref "U14") (pin "12") (pinfunction "GB2_12") (pintype "passive"))
    )
    (net (code "226") (name "unconnected-(U25A-~{Q}-Pad6)") (class "Default")
      (node (ref "U25") (pin "6") (pinfunction "~{Q}_6") (pintype "output"))
    )
  )
)
